# eps.net
KiCad netlist of a schematic drawn in EAGLE
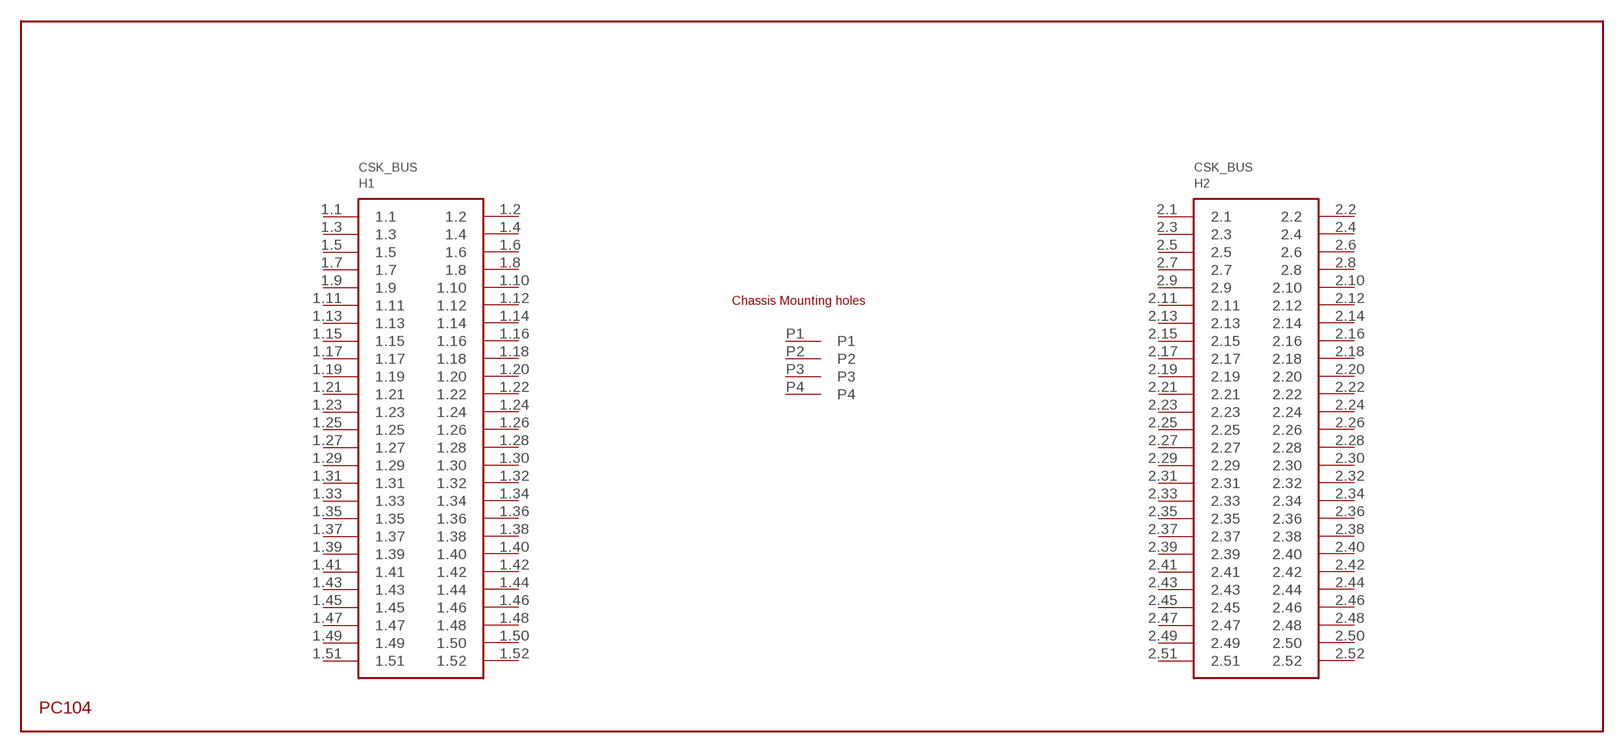
[diagram p0: schematic, sheet 1]
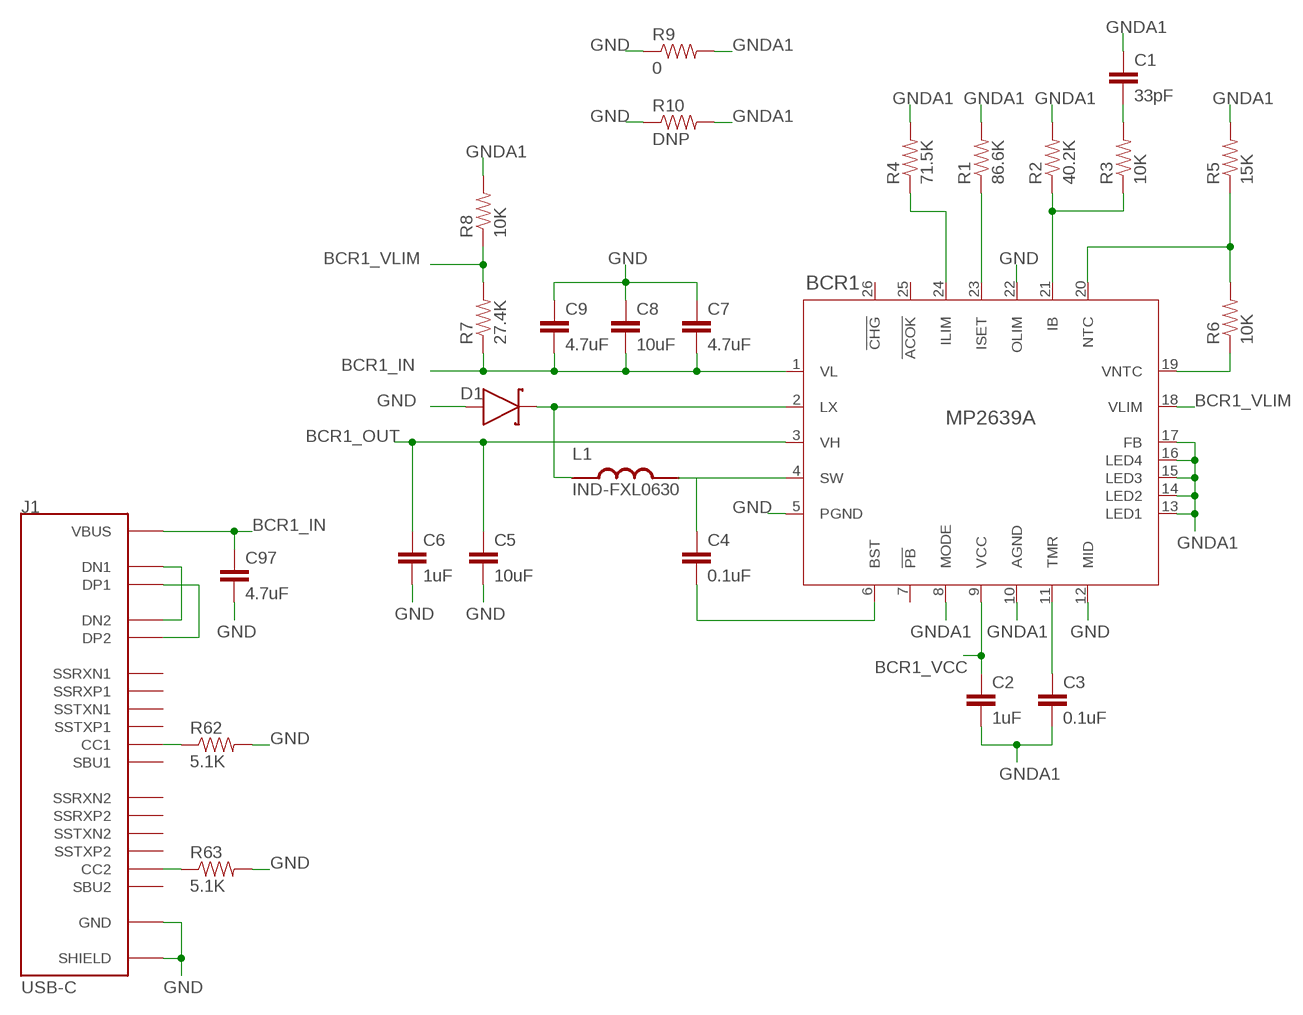
[diagram p1: schematic, sheet 2]
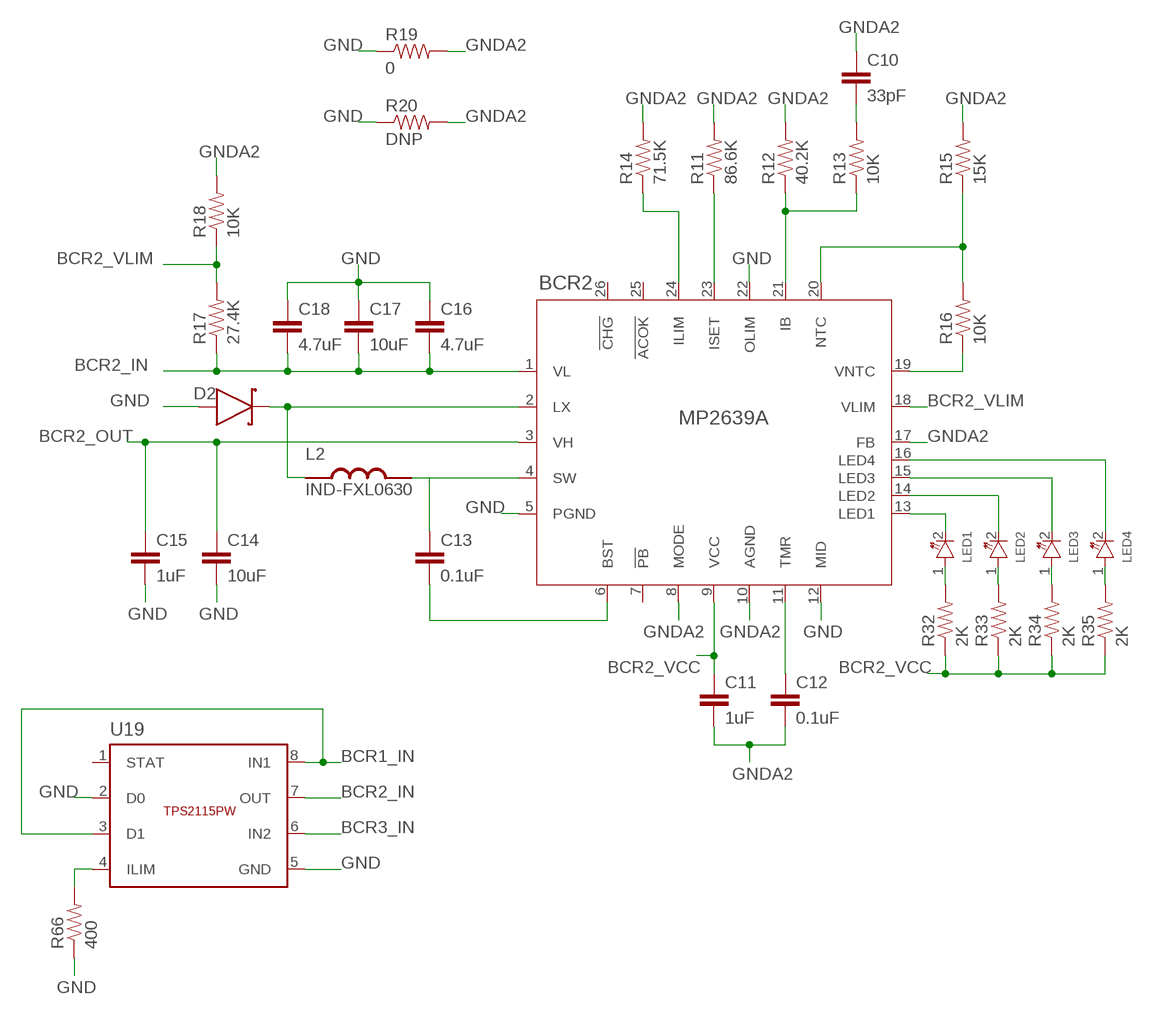
[diagram p2: schematic, sheet 3]
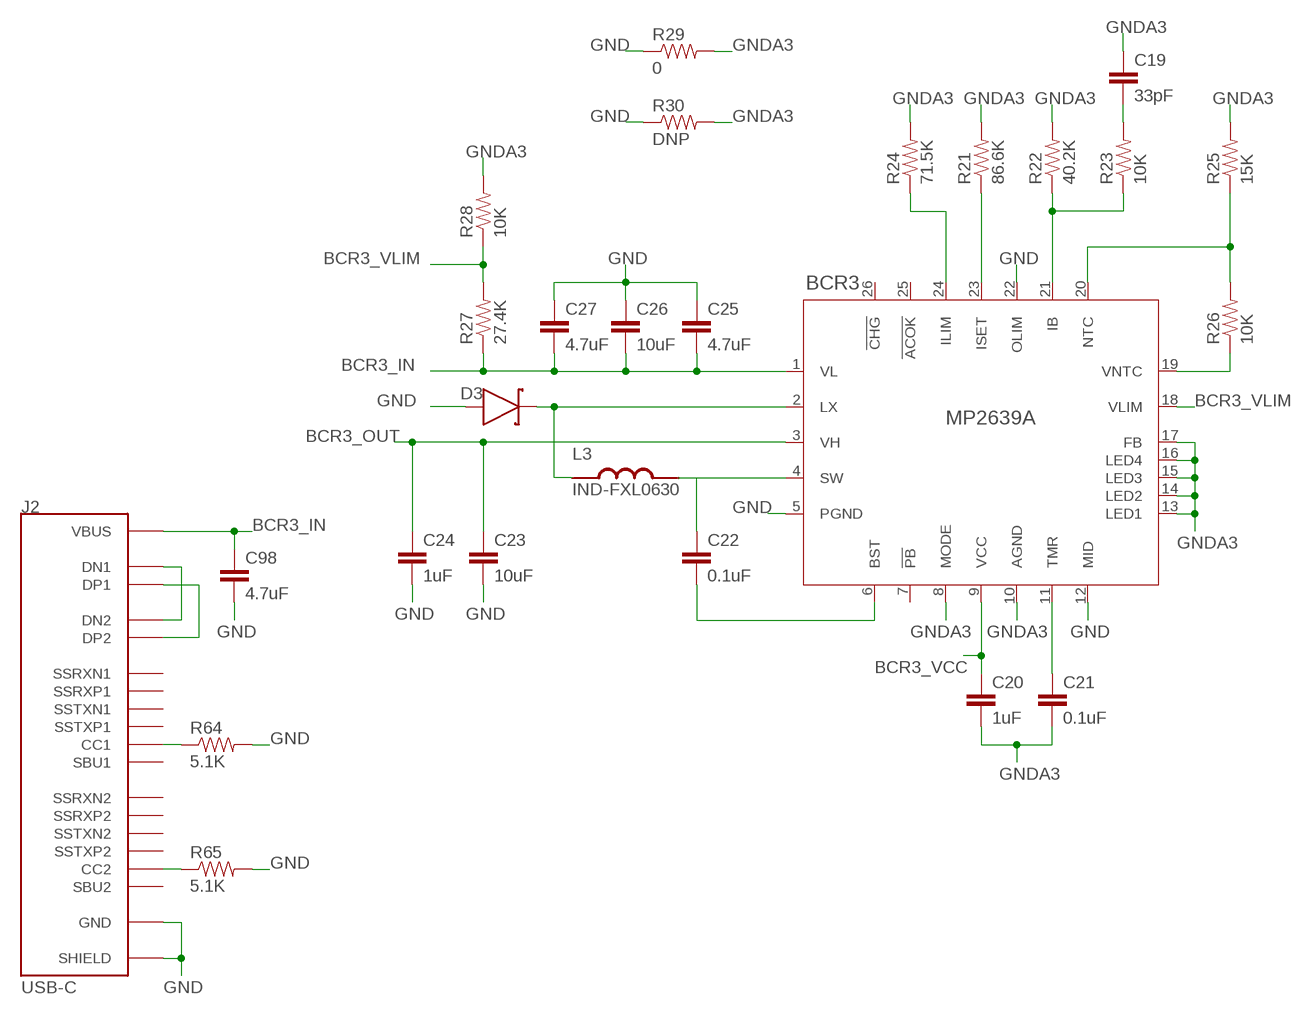
[diagram p3: schematic, sheet 4]
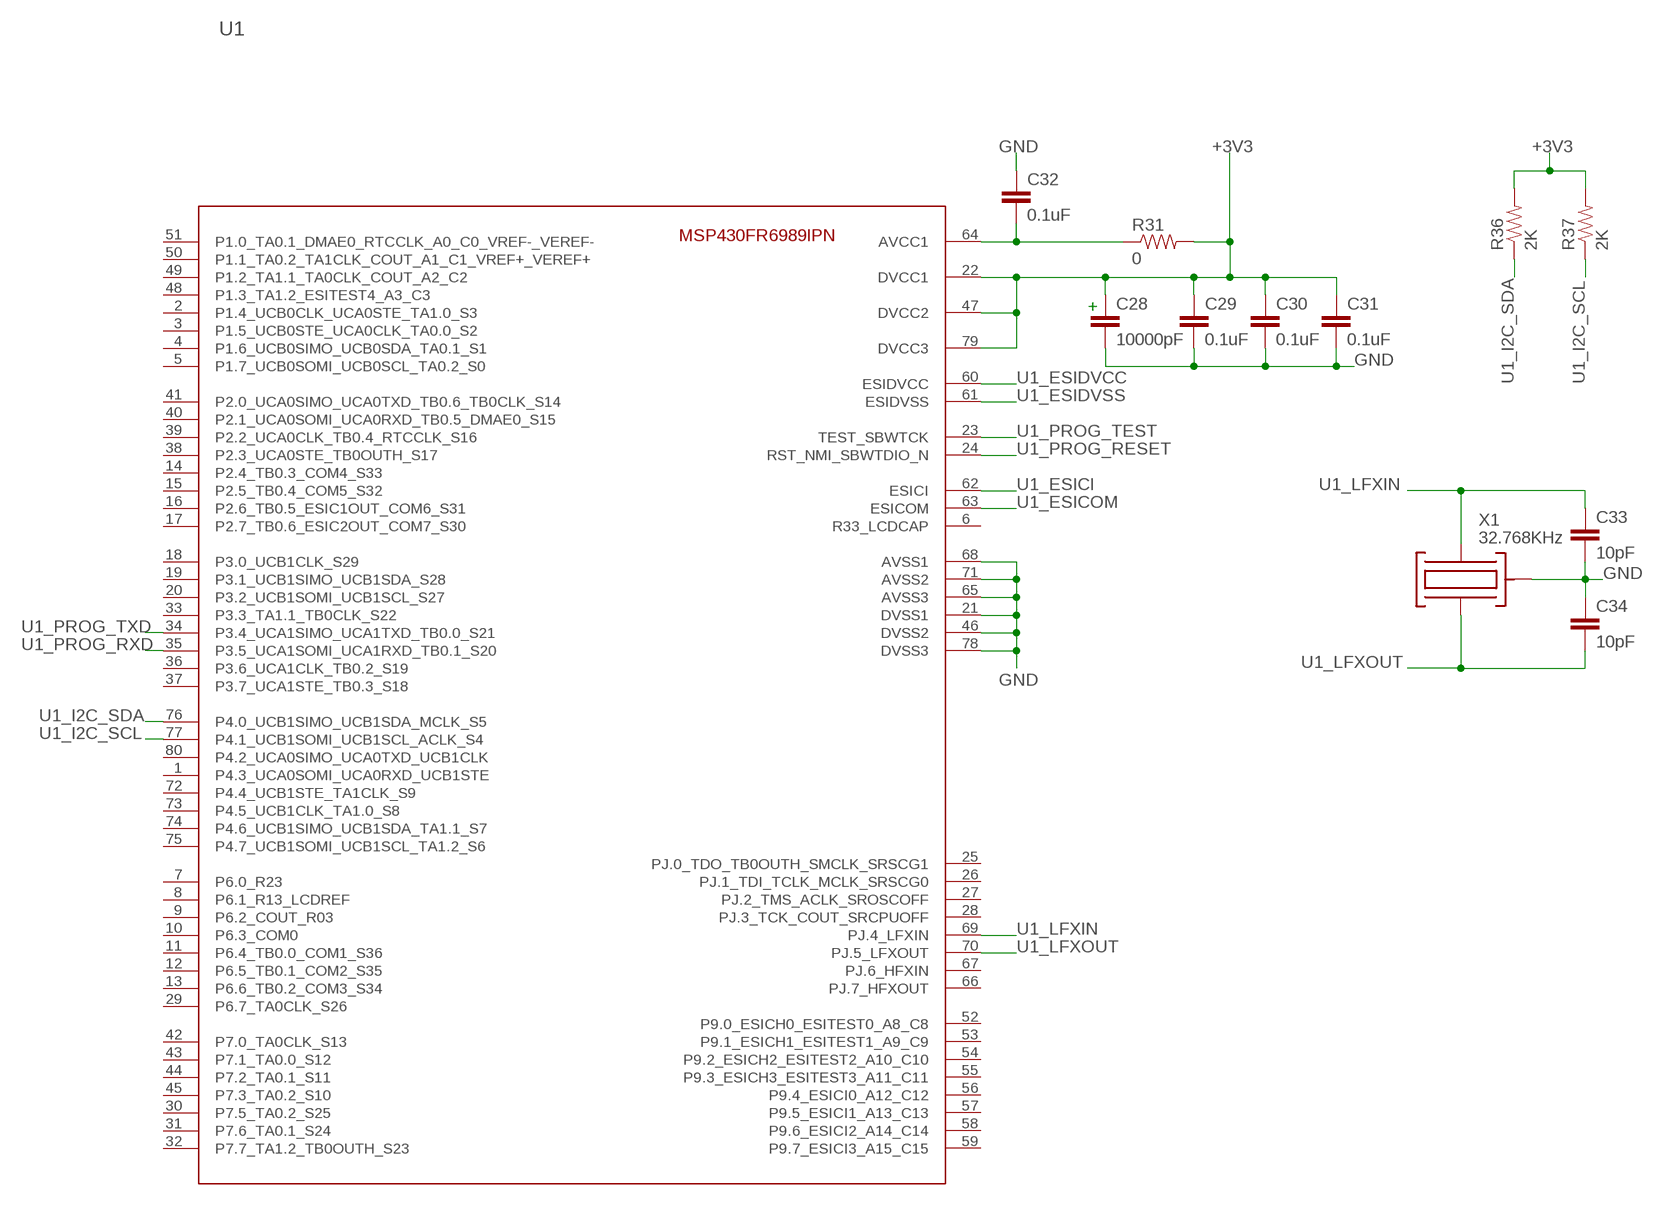
[diagram p4: schematic, sheet 5]
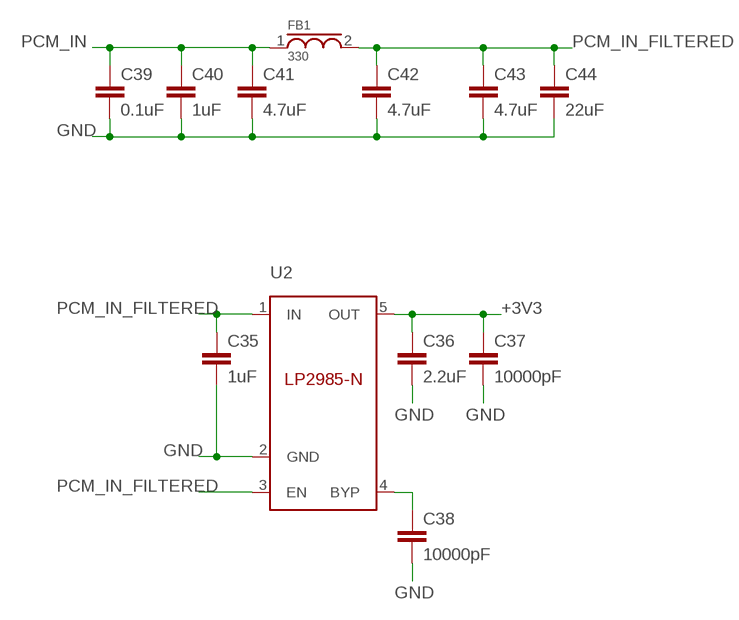
[diagram p5: schematic, sheet 6]
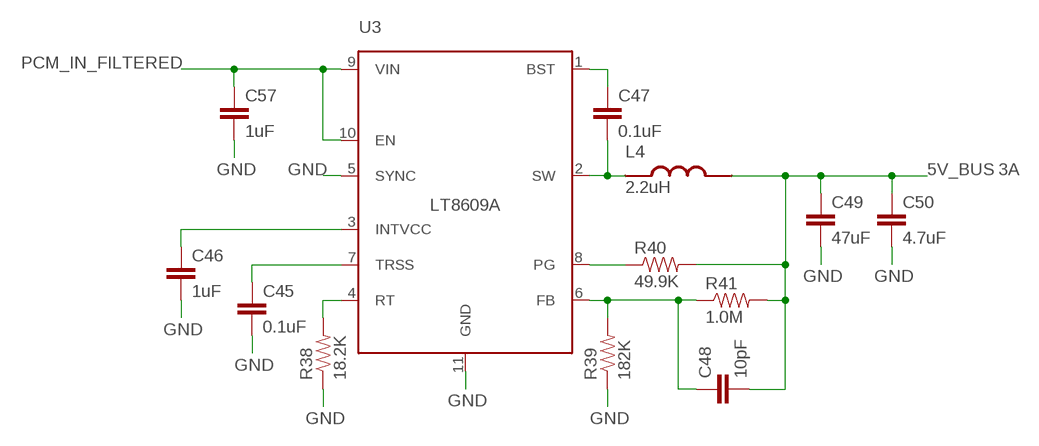
[diagram p6: schematic, sheet 7]
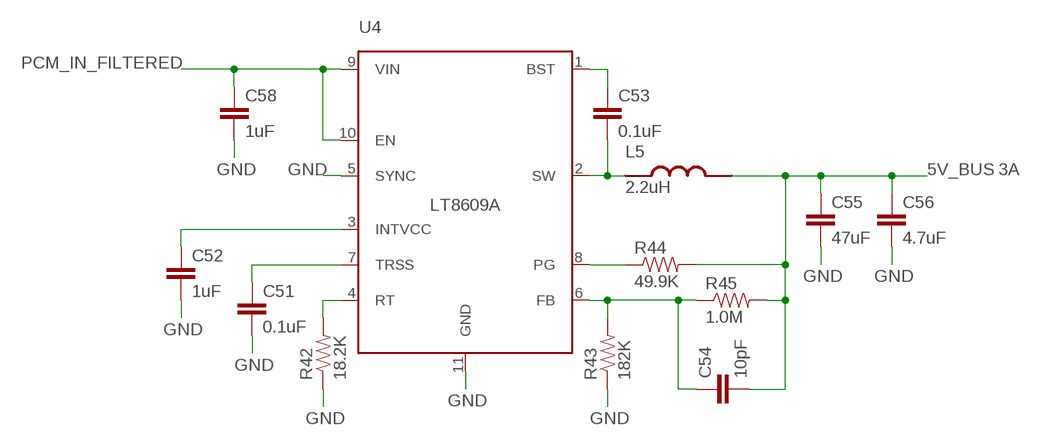
[diagram p7: schematic, sheet 8]
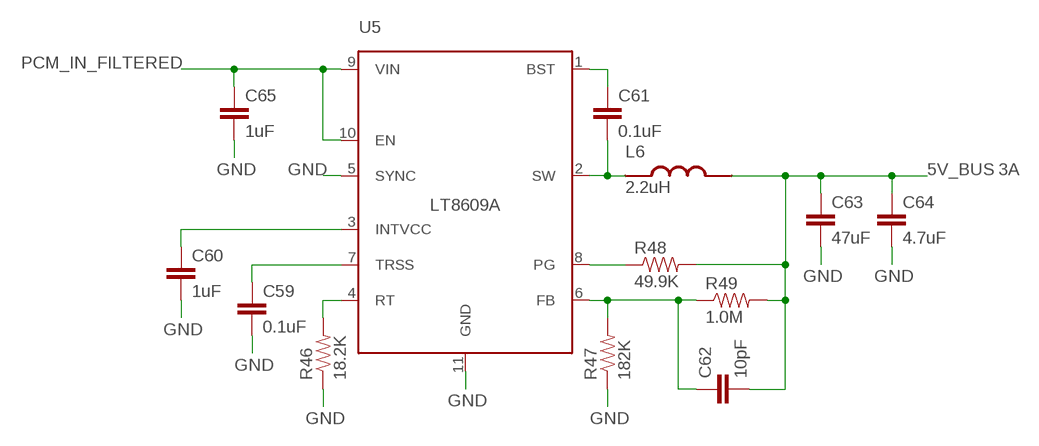
[diagram p8: schematic, sheet 9]
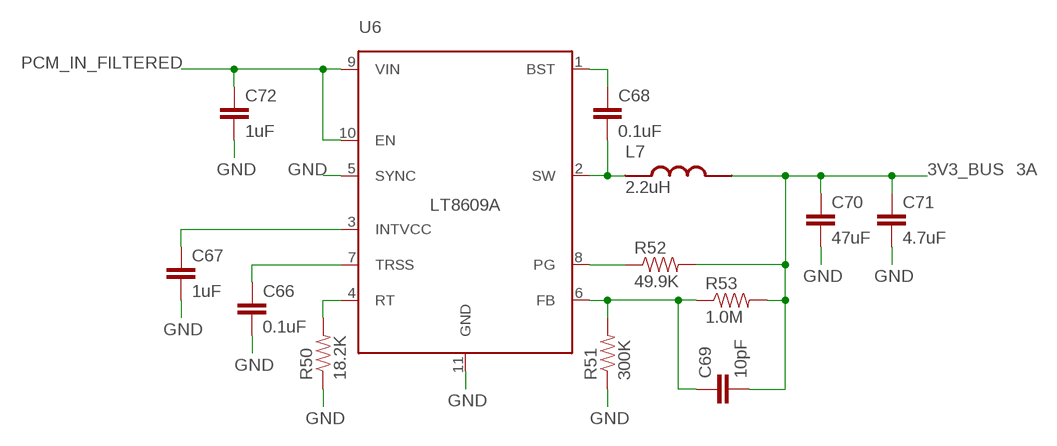
[diagram p9: schematic, sheet 10]
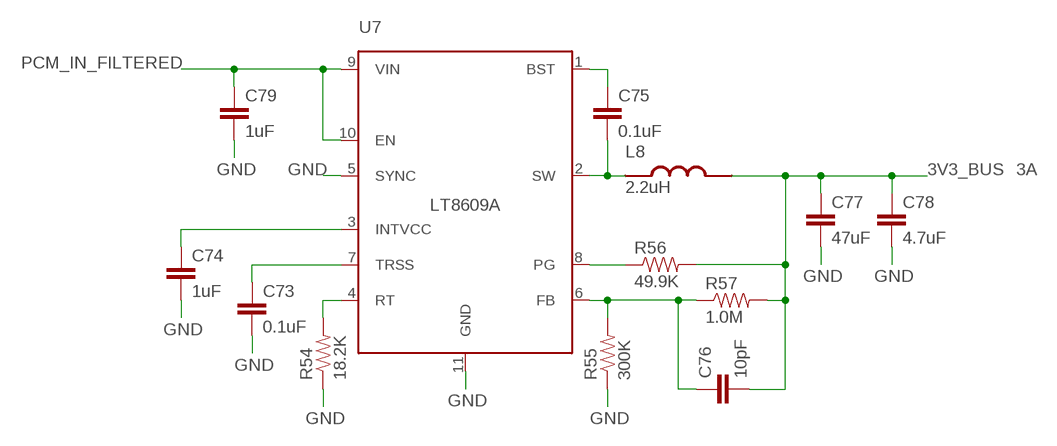
[diagram p10: schematic, sheet 11]
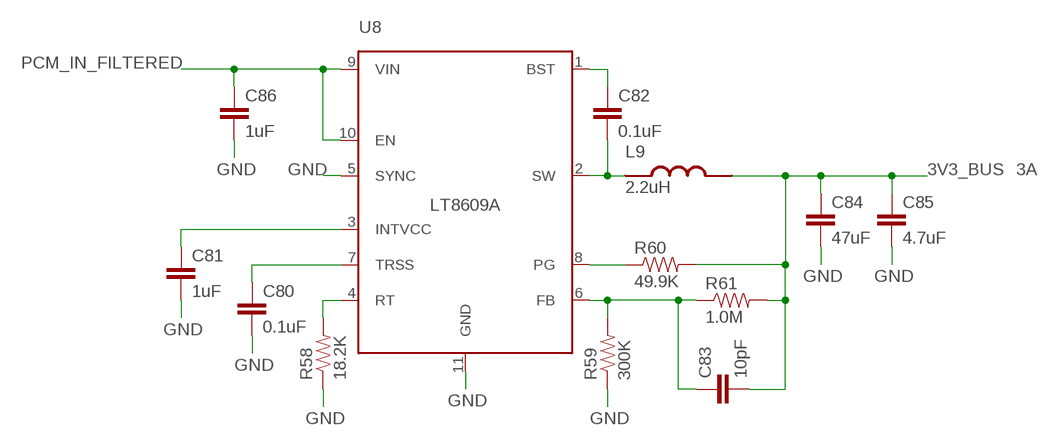
[diagram p11: schematic, sheet 12]
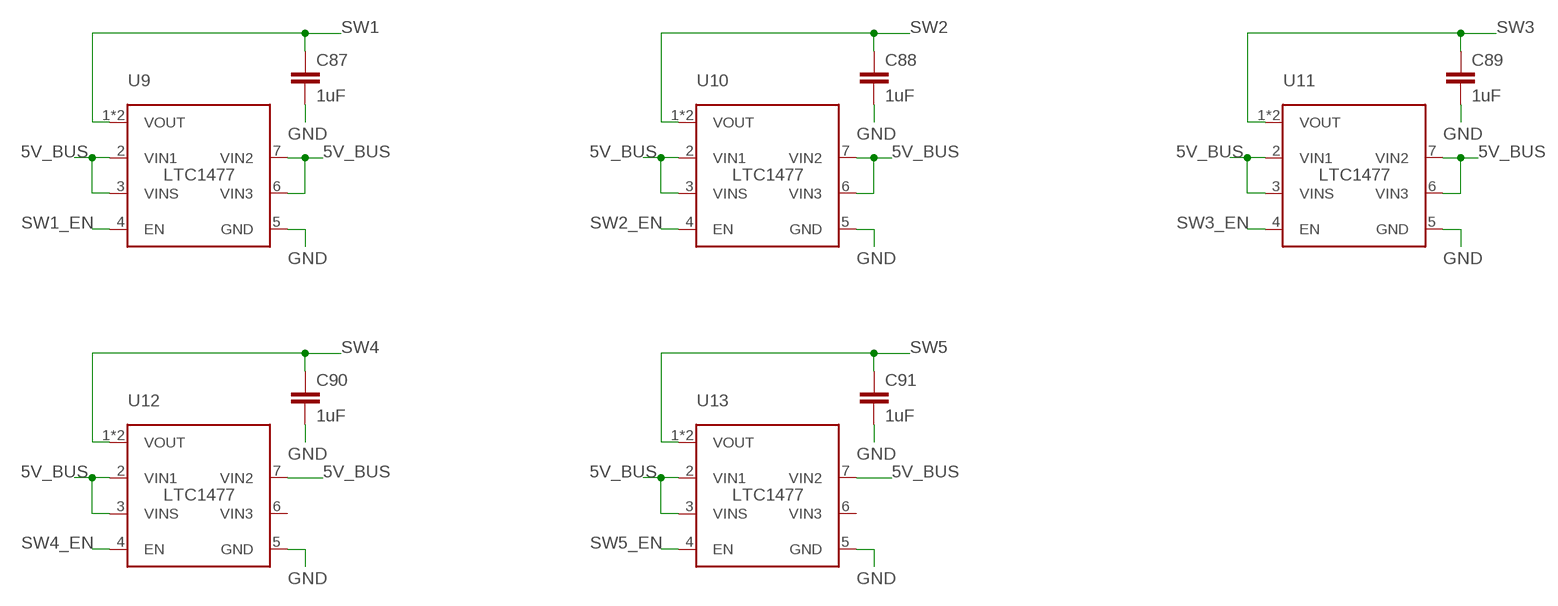
[diagram p12: schematic, sheet 13]
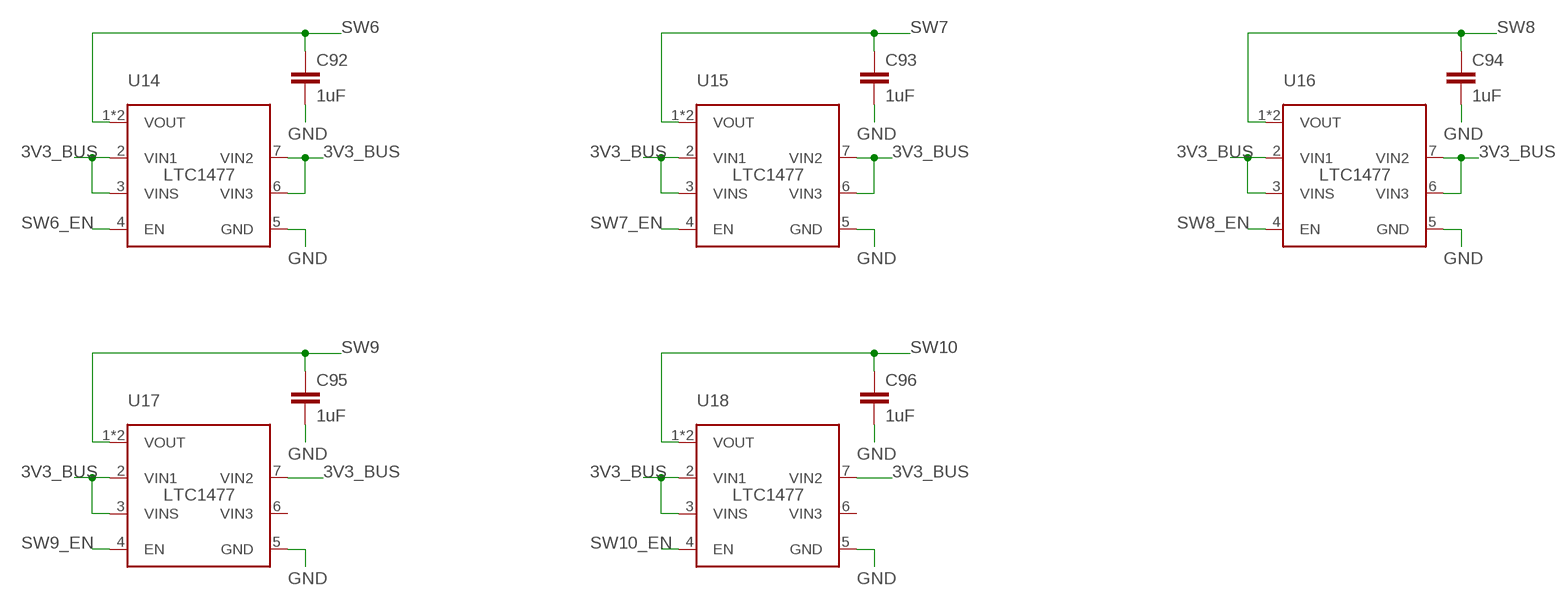
[diagram p13: schematic, sheet 14]

(export (version "E")
  (design (tool "Eeschema 10.0.6"))
  (components
    (comp (ref "H1")
      (value "PC104_WCONN")
      (footprint "eagle-import:PC104_WCONN")
      (libsource (lib "eagle-import") (part "PC104_WCONN"))
    )
    (comp (ref "C51")
      (value "0.1uF")
      (footprint "eagle-import:0603-CAP")
      (libsource (lib "eagle-import") (part "DSD_Passive_Library_CAP0603-CAP"))
    )
    (comp (ref "C52")
      (value "1uF")
      (footprint "eagle-import:0603-CAP")
      (libsource (lib "eagle-import") (part "DSD_Passive_Library_CAP0603-CAP"))
    )
    (comp (ref "C53")
      (value "0.1uF")
      (footprint "eagle-import:0603-CAP")
      (libsource (lib "eagle-import") (part "DSD_Passive_Library_CAP0603-CAP"))
    )
    (comp (ref "C54")
      (value "10pF")
      (footprint "eagle-import:0603-CAP")
      (libsource (lib "eagle-import") (part "DSD_Passive_Library_CAP0603-CAP"))
    )
    (comp (ref "C55")
      (value "47uF")
      (footprint "eagle-import:0805")
      (libsource (lib "eagle-import") (part "DSD_Passive_Library_CAP0805"))
    )
    (comp (ref "C56")
      (value "4.7uF")
      (footprint "eagle-import:0603-CAP")
      (libsource (lib "eagle-import") (part "DSD_Passive_Library_CAP0603-CAP"))
    )
    (comp (ref "C58")
      (value "1uF")
      (footprint "eagle-import:0603-CAP")
      (libsource (lib "eagle-import") (part "DSD_Passive_Library_CAP0603-CAP"))
    )
    (comp (ref "L5")
      (value "2.2uH")
      (footprint "eagle-import:XFL4020")
      (libsource (lib "eagle-import") (part "IND-XFL4020"))
    )
    (comp (ref "R42")
      (value "18.2K")
      (footprint "eagle-import:0603-RES")
      (libsource (lib "eagle-import") (part "RESISTOR0603-RES"))
    )
    (comp (ref "R43")
      (value "182K")
      (footprint "eagle-import:0603-RES")
      (libsource (lib "eagle-import") (part "RESISTOR0603-RES"))
    )
    (comp (ref "R44")
      (value "49.9K")
      (footprint "eagle-import:0603-RES")
      (libsource (lib "eagle-import") (part "RESISTOR0603-RES"))
    )
    (comp (ref "R45")
      (value "1.0M")
      (footprint "eagle-import:0603-RES")
      (libsource (lib "eagle-import") (part "RESISTOR0603-RES"))
    )
    (comp (ref "U4")
      (value "LT8609A")
      (footprint "eagle-import:MSOP-10_MSE")
      (libsource (lib "eagle-import") (part "LT8609A"))
    )
    (comp (ref "C87")
      (value "1uF")
      (footprint "eagle-import:0603-CAP")
      (libsource (lib "eagle-import") (part "DSD_Passive_Library_CAP0603-CAP"))
    )
    (comp (ref "C88")
      (value "1uF")
      (footprint "eagle-import:0603-CAP")
      (libsource (lib "eagle-import") (part "DSD_Passive_Library_CAP0603-CAP"))
    )
    (comp (ref "C89")
      (value "1uF")
      (footprint "eagle-import:0603-CAP")
      (libsource (lib "eagle-import") (part "DSD_Passive_Library_CAP0603-CAP"))
    )
    (comp (ref "C90")
      (value "1uF")
      (footprint "eagle-import:0603-CAP")
      (libsource (lib "eagle-import") (part "DSD_Passive_Library_CAP0603-CAP"))
    )
    (comp (ref "C91")
      (value "1uF")
      (footprint "eagle-import:0603-CAP")
      (libsource (lib "eagle-import") (part "DSD_Passive_Library_CAP0603-CAP"))
    )
    (comp (ref "U9")
      (value "LTC1477")
      (footprint "eagle-import:SO8")
      (libsource (lib "eagle-import") (part "LTC1477"))
    )
    (comp (ref "U10")
      (value "LTC1477")
      (footprint "eagle-import:SO8")
      (libsource (lib "eagle-import") (part "LTC1477"))
    )
    (comp (ref "U11")
      (value "LTC1477")
      (footprint "eagle-import:SO8")
      (libsource (lib "eagle-import") (part "LTC1477"))
    )
    (comp (ref "U12")
      (value "LTC1477")
      (footprint "eagle-import:SO8")
      (libsource (lib "eagle-import") (part "LTC1477"))
    )
    (comp (ref "U13")
      (value "LTC1477")
      (footprint "eagle-import:SO8")
      (libsource (lib "eagle-import") (part "LTC1477"))
    )
    (comp (ref "BCR2")
      (value "MP2639A")
      (footprint "eagle-import:IC26_MP2639A_MNP")
      (fields (field (name "COPYRIGHT") "Copyright (C) 2021 DSD. All rights reserved"))
      (libsource (lib "eagle-import") (part "MP2639A"))
    )
    (comp (ref "C10")
      (value "33pF")
      (footprint "eagle-import:0603-CAP")
      (libsource (lib "eagle-import") (part "CAP0603-CAP"))
    )
    (comp (ref "C11")
      (value "1uF")
      (footprint "eagle-import:0603-CAP")
      (libsource (lib "eagle-import") (part "CAP0603-CAP"))
    )
    (comp (ref "C12")
      (value "0.1uF")
      (footprint "eagle-import:0603-CAP")
      (libsource (lib "eagle-import") (part "CAP0603-CAP"))
    )
    (comp (ref "C13")
      (value "0.1uF")
      (footprint "eagle-import:0603-CAP")
      (libsource (lib "eagle-import") (part "CAP0603-CAP"))
    )
    (comp (ref "C14")
      (value "10uF")
      (footprint "eagle-import:0603-CAP")
      (libsource (lib "eagle-import") (part "CAP0603-CAP"))
    )
    (comp (ref "C15")
      (value "1uF")
      (footprint "eagle-import:0603-CAP")
      (libsource (lib "eagle-import") (part "CAP0603-CAP"))
    )
    (comp (ref "C16")
      (value "4.7uF")
      (footprint "eagle-import:0603-CAP")
      (libsource (lib "eagle-import") (part "CAP0603-CAP"))
    )
    (comp (ref "C17")
      (value "10uF")
      (footprint "eagle-import:0603-CAP")
      (libsource (lib "eagle-import") (part "CAP0603-CAP"))
    )
    (comp (ref "C18")
      (value "4.7uF")
      (footprint "eagle-import:0603-CAP")
      (libsource (lib "eagle-import") (part "CAP0603-CAP"))
    )
    (comp (ref "D2")
      (value "DIODE-SOD123")
      (footprint "eagle-import:SOD123")
      (libsource (lib "eagle-import") (part "DIODE-SOD123"))
    )
    (comp (ref "L2")
      (value "IND-FXL0630")
      (footprint "eagle-import:FXL0630")
      (libsource (lib "eagle-import") (part "IND-FXL0630"))
    )
    (comp (ref "LED1")
      (value "LED_0805")
      (footprint "eagle-import:LED_0805")
      (libsource (lib "eagle-import") (part "LED_0805"))
    )
    (comp (ref "LED2")
      (value "LED_0805")
      (footprint "eagle-import:LED_0805")
      (libsource (lib "eagle-import") (part "LED_0805"))
    )
    (comp (ref "LED3")
      (value "LED_0805")
      (footprint "eagle-import:LED_0805")
      (libsource (lib "eagle-import") (part "LED_0805"))
    )
    (comp (ref "LED4")
      (value "LED_0805")
      (footprint "eagle-import:LED_0805")
      (libsource (lib "eagle-import") (part "LED_0805"))
    )
    (comp (ref "R11")
      (value "86.6K")
      (footprint "eagle-import:0603-RES")
      (libsource (lib "eagle-import") (part "RESISTOR0603-RES"))
    )
    (comp (ref "R12")
      (value "40.2K")
      (footprint "eagle-import:0603-RES")
      (libsource (lib "eagle-import") (part "RESISTOR0603-RES"))
    )
    (comp (ref "R13")
      (value "10K")
      (footprint "eagle-import:0603-RES")
      (libsource (lib "eagle-import") (part "RESISTOR0603-RES"))
    )
    (comp (ref "R14")
      (value "71.5K")
      (footprint "eagle-import:0603-RES")
      (libsource (lib "eagle-import") (part "RESISTOR0603-RES"))
    )
    (comp (ref "R15")
      (value "15K")
      (footprint "eagle-import:0603-RES")
      (libsource (lib "eagle-import") (part "RESISTOR0603-RES"))
    )
    (comp (ref "R16")
      (value "10K")
      (footprint "eagle-import:0603-RES")
      (libsource (lib "eagle-import") (part "RESISTOR0603-RES"))
    )
    (comp (ref "R17")
      (value "27.4K")
      (footprint "eagle-import:0603-RES")
      (libsource (lib "eagle-import") (part "RESISTOR0603-RES"))
    )
    (comp (ref "R18")
      (value "10K")
      (footprint "eagle-import:0603-RES")
      (libsource (lib "eagle-import") (part "RESISTOR0603-RES"))
    )
    (comp (ref "R19")
      (value "0")
      (footprint "eagle-import:0603-RES")
      (libsource (lib "eagle-import") (part "RESISTOR0603-RES"))
    )
    (comp (ref "R20")
      (value "DNP")
      (footprint "eagle-import:0603-RES")
      (libsource (lib "eagle-import") (part "RESISTOR0603-RES"))
    )
    (comp (ref "R32")
      (value "2K")
      (footprint "eagle-import:0603-RES")
      (libsource (lib "eagle-import") (part "RESISTOR0603-RES"))
    )
    (comp (ref "R33")
      (value "2K")
      (footprint "eagle-import:0603-RES")
      (libsource (lib "eagle-import") (part "RESISTOR0603-RES"))
    )
    (comp (ref "R34")
      (value "2K")
      (footprint "eagle-import:0603-RES")
      (libsource (lib "eagle-import") (part "RESISTOR0603-RES"))
    )
    (comp (ref "R35")
      (value "2K")
      (footprint "eagle-import:0603-RES")
      (libsource (lib "eagle-import") (part "RESISTOR0603-RES"))
    )
    (comp (ref "R66")
      (value "400")
      (footprint "eagle-import:0603-RES")
      (libsource (lib "eagle-import") (part "RESISTOR0603-RES"))
    )
    (comp (ref "U19")
      (value "TPS2115PW")
      (footprint "eagle-import:TTSOP-8")
      (libsource (lib "eagle-import") (part "TPS2115PW"))
    )
    (comp (ref "C45")
      (value "0.1uF")
      (footprint "eagle-import:0603-CAP")
      (libsource (lib "eagle-import") (part "DSD_Passive_Library_CAP0603-CAP"))
    )
    (comp (ref "C46")
      (value "1uF")
      (footprint "eagle-import:0603-CAP")
      (libsource (lib "eagle-import") (part "DSD_Passive_Library_CAP0603-CAP"))
    )
    (comp (ref "C47")
      (value "0.1uF")
      (footprint "eagle-import:0603-CAP")
      (libsource (lib "eagle-import") (part "DSD_Passive_Library_CAP0603-CAP"))
    )
    (comp (ref "C48")
      (value "10pF")
      (footprint "eagle-import:0603-CAP")
      (libsource (lib "eagle-import") (part "DSD_Passive_Library_CAP0603-CAP"))
    )
    (comp (ref "C49")
      (value "47uF")
      (footprint "eagle-import:0805")
      (libsource (lib "eagle-import") (part "DSD_Passive_Library_CAP0805"))
    )
    (comp (ref "C50")
      (value "4.7uF")
      (footprint "eagle-import:0603-CAP")
      (libsource (lib "eagle-import") (part "DSD_Passive_Library_CAP0603-CAP"))
    )
    (comp (ref "C57")
      (value "1uF")
      (footprint "eagle-import:0603-CAP")
      (libsource (lib "eagle-import") (part "DSD_Passive_Library_CAP0603-CAP"))
    )
    (comp (ref "L4")
      (value "2.2uH")
      (footprint "eagle-import:XFL4020")
      (libsource (lib "eagle-import") (part "IND-XFL4020"))
    )
    (comp (ref "R38")
      (value "18.2K")
      (footprint "eagle-import:0603-RES")
      (libsource (lib "eagle-import") (part "RESISTOR0603-RES"))
    )
    (comp (ref "R39")
      (value "182K")
      (footprint "eagle-import:0603-RES")
      (libsource (lib "eagle-import") (part "RESISTOR0603-RES"))
    )
    (comp (ref "R40")
      (value "49.9K")
      (footprint "eagle-import:0603-RES")
      (libsource (lib "eagle-import") (part "RESISTOR0603-RES"))
    )
    (comp (ref "R41")
      (value "1.0M")
      (footprint "eagle-import:0603-RES")
      (libsource (lib "eagle-import") (part "RESISTOR0603-RES"))
    )
    (comp (ref "U3")
      (value "LT8609A")
      (footprint "eagle-import:MSOP-10_MSE")
      (libsource (lib "eagle-import") (part "LT8609A"))
    )
    (comp (ref "C35")
      (value "1uF")
      (footprint "eagle-import:0603-CAP")
      (libsource (lib "eagle-import") (part "DSD_Passive_Library_CAP0603-CAP"))
    )
    (comp (ref "C36")
      (value "2.2uF")
      (footprint "eagle-import:0603-CAP")
      (libsource (lib "eagle-import") (part "DSD_Passive_Library_CAP0603-CAP"))
    )
    (comp (ref "C37")
      (value "10000pF")
      (footprint "eagle-import:0603-CAP")
      (libsource (lib "eagle-import") (part "DSD_Passive_Library_CAP0603-CAP"))
    )
    (comp (ref "C38")
      (value "10000pF")
      (footprint "eagle-import:0603-CAP")
      (libsource (lib "eagle-import") (part "DSD_Passive_Library_CAP0603-CAP"))
    )
    (comp (ref "C39")
      (value "0.1uF")
      (footprint "eagle-import:0603-CAP")
      (libsource (lib "eagle-import") (part "DSD_Passive_Library_CAP0603-CAP"))
    )
    (comp (ref "C40")
      (value "1uF")
      (footprint "eagle-import:0603-CAP")
      (libsource (lib "eagle-import") (part "DSD_Passive_Library_CAP0603-CAP"))
    )
    (comp (ref "C41")
      (value "4.7uF")
      (footprint "eagle-import:1206")
      (libsource (lib "eagle-import") (part "DSD_Passive_Library_CAP1206"))
    )
    (comp (ref "C42")
      (value "4.7uF")
      (footprint "eagle-import:1206")
      (libsource (lib "eagle-import") (part "DSD_Passive_Library_CAP1206"))
    )
    (comp (ref "C43")
      (value "4.7uF")
      (footprint "eagle-import:1206")
      (libsource (lib "eagle-import") (part "DSD_Passive_Library_CAP1206"))
    )
    (comp (ref "C44")
      (value "22uF")
      (footprint "eagle-import:2917")
      (libsource (lib "eagle-import") (part "CAP_TANTALUM"))
    )
    (comp (ref "FB1")
      (value "330")
      (footprint "eagle-import:0805")
      (libsource (lib "eagle-import") (part "FB0805"))
    )
    (comp (ref "U2")
      (value "LP2985-N")
      (footprint "eagle-import:SOT23-5")
      (libsource (lib "eagle-import") (part "LP2985-N"))
    )
    (comp (ref "C66")
      (value "0.1uF")
      (footprint "eagle-import:0603-CAP")
      (libsource (lib "eagle-import") (part "DSD_Passive_Library_CAP0603-CAP"))
    )
    (comp (ref "C67")
      (value "1uF")
      (footprint "eagle-import:0603-CAP")
      (libsource (lib "eagle-import") (part "DSD_Passive_Library_CAP0603-CAP"))
    )
    (comp (ref "C68")
      (value "0.1uF")
      (footprint "eagle-import:0603-CAP")
      (libsource (lib "eagle-import") (part "DSD_Passive_Library_CAP0603-CAP"))
    )
    (comp (ref "C69")
      (value "10pF")
      (footprint "eagle-import:0603-CAP")
      (libsource (lib "eagle-import") (part "DSD_Passive_Library_CAP0603-CAP"))
    )
    (comp (ref "C70")
      (value "47uF")
      (footprint "eagle-import:0805")
      (libsource (lib "eagle-import") (part "DSD_Passive_Library_CAP0805"))
    )
    (comp (ref "C71")
      (value "4.7uF")
      (footprint "eagle-import:0603-CAP")
      (libsource (lib "eagle-import") (part "DSD_Passive_Library_CAP0603-CAP"))
    )
    (comp (ref "C72")
      (value "1uF")
      (footprint "eagle-import:0603-CAP")
      (libsource (lib "eagle-import") (part "DSD_Passive_Library_CAP0603-CAP"))
    )
    (comp (ref "L7")
      (value "2.2uH")
      (footprint "eagle-import:XFL4020")
      (libsource (lib "eagle-import") (part "IND-XFL4020"))
    )
    (comp (ref "R50")
      (value "18.2K")
      (footprint "eagle-import:0603-RES")
      (libsource (lib "eagle-import") (part "RESISTOR0603-RES"))
    )
    (comp (ref "R51")
      (value "300K")
      (footprint "eagle-import:0603-RES")
      (libsource (lib "eagle-import") (part "RESISTOR0603-RES"))
    )
    (comp (ref "R52")
      (value "49.9K")
      (footprint "eagle-import:0603-RES")
      (libsource (lib "eagle-import") (part "RESISTOR0603-RES"))
    )
    (comp (ref "R53")
      (value "1.0M")
      (footprint "eagle-import:0603-RES")
      (libsource (lib "eagle-import") (part "RESISTOR0603-RES"))
    )
    (comp (ref "U6")
      (value "LT8609A")
      (footprint "eagle-import:MSOP-10_MSE")
      (libsource (lib "eagle-import") (part "LT8609A"))
    )
    (comp (ref "BCR1")
      (value "MP2639A")
      (footprint "eagle-import:IC26_MP2639A_MNP")
      (fields (field (name "COPYRIGHT") "Copyright (C) 2021 DSD. All rights reserved"))
      (libsource (lib "eagle-import") (part "MP2639A"))
    )
    (comp (ref "C1")
      (value "33pF")
      (footprint "eagle-import:0603-CAP")
      (libsource (lib "eagle-import") (part "CAP0603-CAP"))
    )
    (comp (ref "C2")
      (value "1uF")
      (footprint "eagle-import:0603-CAP")
      (libsource (lib "eagle-import") (part "CAP0603-CAP"))
    )
    (comp (ref "C3")
      (value "0.1uF")
      (footprint "eagle-import:0603-CAP")
      (libsource (lib "eagle-import") (part "CAP0603-CAP"))
    )
    (comp (ref "C4")
      (value "0.1uF")
      (footprint "eagle-import:0603-CAP")
      (libsource (lib "eagle-import") (part "CAP0603-CAP"))
    )
    (comp (ref "C5")
      (value "10uF")
      (footprint "eagle-import:0603-CAP")
      (libsource (lib "eagle-import") (part "CAP0603-CAP"))
    )
    (comp (ref "C6")
      (value "1uF")
      (footprint "eagle-import:0603-CAP")
      (libsource (lib "eagle-import") (part "CAP0603-CAP"))
    )
    (comp (ref "C7")
      (value "4.7uF")
      (footprint "eagle-import:0603-CAP")
      (libsource (lib "eagle-import") (part "CAP0603-CAP"))
    )
    (comp (ref "C8")
      (value "10uF")
      (footprint "eagle-import:0603-CAP")
      (libsource (lib "eagle-import") (part "CAP0603-CAP"))
    )
    (comp (ref "C9")
      (value "4.7uF")
      (footprint "eagle-import:0603-CAP")
      (libsource (lib "eagle-import") (part "CAP0603-CAP"))
    )
    (comp (ref "C97")
      (value "4.7uF")
      (footprint "eagle-import:0603-CAP")
      (libsource (lib "eagle-import") (part "DSD_Passive_Library_CAP0603-CAP"))
    )
    (comp (ref "D1")
      (value "DIODE-SOD123")
      (footprint "eagle-import:SOD123")
      (libsource (lib "eagle-import") (part "DIODE-SOD123"))
    )
    (comp (ref "J1")
      (value "USB-C")
      (footprint "eagle-import:CUI_UJ31-CH-G1-SMT-TR")
      (fields (field (name "MF") "CUI Devices") (field (name "MP") "UJ31-CH-G1-SMT-TR"))
      (libsource (lib "eagle-import") (part "USB-C"))
    )
    (comp (ref "L1")
      (value "IND-FXL0630")
      (footprint "eagle-import:FXL0630")
      (libsource (lib "eagle-import") (part "IND-FXL0630"))
    )
    (comp (ref "R1")
      (value "86.6K")
      (footprint "eagle-import:0603-RES")
      (libsource (lib "eagle-import") (part "RESISTOR0603-RES"))
    )
    (comp (ref "R2")
      (value "40.2K")
      (footprint "eagle-import:0603-RES")
      (libsource (lib "eagle-import") (part "RESISTOR0603-RES"))
    )
    (comp (ref "R3")
      (value "10K")
      (footprint "eagle-import:0603-RES")
      (libsource (lib "eagle-import") (part "RESISTOR0603-RES"))
    )
    (comp (ref "R4")
      (value "71.5K")
      (footprint "eagle-import:0603-RES")
      (libsource (lib "eagle-import") (part "RESISTOR0603-RES"))
    )
    (comp (ref "R5")
      (value "15K")
      (footprint "eagle-import:0603-RES")
      (libsource (lib "eagle-import") (part "RESISTOR0603-RES"))
    )
    (comp (ref "R6")
      (value "10K")
      (footprint "eagle-import:0603-RES")
      (libsource (lib "eagle-import") (part "RESISTOR0603-RES"))
    )
    (comp (ref "R7")
      (value "27.4K")
      (footprint "eagle-import:0603-RES")
      (libsource (lib "eagle-import") (part "RESISTOR0603-RES"))
    )
    (comp (ref "R8")
      (value "10K")
      (footprint "eagle-import:0603-RES")
      (libsource (lib "eagle-import") (part "RESISTOR0603-RES"))
    )
    (comp (ref "R9")
      (value "0")
      (footprint "eagle-import:0603-RES")
      (libsource (lib "eagle-import") (part "RESISTOR0603-RES"))
    )
    (comp (ref "R10")
      (value "DNP")
      (footprint "eagle-import:0603-RES")
      (libsource (lib "eagle-import") (part "RESISTOR0603-RES"))
    )
    (comp (ref "R62")
      (value "5.1K")
      (footprint "eagle-import:0603-RES")
      (libsource (lib "eagle-import") (part "RESISTOR0603-RES"))
    )
    (comp (ref "R63")
      (value "5.1K")
      (footprint "eagle-import:0603-RES")
      (libsource (lib "eagle-import") (part "RESISTOR0603-RES"))
    )
    (comp (ref "C59")
      (value "0.1uF")
      (footprint "eagle-import:0603-CAP")
      (libsource (lib "eagle-import") (part "DSD_Passive_Library_CAP0603-CAP"))
    )
    (comp (ref "C60")
      (value "1uF")
      (footprint "eagle-import:0603-CAP")
      (libsource (lib "eagle-import") (part "DSD_Passive_Library_CAP0603-CAP"))
    )
    (comp (ref "C61")
      (value "0.1uF")
      (footprint "eagle-import:0603-CAP")
      (libsource (lib "eagle-import") (part "DSD_Passive_Library_CAP0603-CAP"))
    )
    (comp (ref "C62")
      (value "10pF")
      (footprint "eagle-import:0603-CAP")
      (libsource (lib "eagle-import") (part "DSD_Passive_Library_CAP0603-CAP"))
    )
    (comp (ref "C63")
      (value "47uF")
      (footprint "eagle-import:0805")
      (libsource (lib "eagle-import") (part "DSD_Passive_Library_CAP0805"))
    )
    (comp (ref "C64")
      (value "4.7uF")
      (footprint "eagle-import:0603-CAP")
      (libsource (lib "eagle-import") (part "DSD_Passive_Library_CAP0603-CAP"))
    )
    (comp (ref "C65")
      (value "1uF")
      (footprint "eagle-import:0603-CAP")
      (libsource (lib "eagle-import") (part "DSD_Passive_Library_CAP0603-CAP"))
    )
    (comp (ref "L6")
      (value "2.2uH")
      (footprint "eagle-import:XFL4020")
      (libsource (lib "eagle-import") (part "IND-XFL4020"))
    )
    (comp (ref "R46")
      (value "18.2K")
      (footprint "eagle-import:0603-RES")
      (libsource (lib "eagle-import") (part "RESISTOR0603-RES"))
    )
    (comp (ref "R47")
      (value "182K")
      (footprint "eagle-import:0603-RES")
      (libsource (lib "eagle-import") (part "RESISTOR0603-RES"))
    )
    (comp (ref "R48")
      (value "49.9K")
      (footprint "eagle-import:0603-RES")
      (libsource (lib "eagle-import") (part "RESISTOR0603-RES"))
    )
    (comp (ref "R49")
      (value "1.0M")
      (footprint "eagle-import:0603-RES")
      (libsource (lib "eagle-import") (part "RESISTOR0603-RES"))
    )
    (comp (ref "U5")
      (value "LT8609A")
      (footprint "eagle-import:MSOP-10_MSE")
      (libsource (lib "eagle-import") (part "LT8609A"))
    )
    (comp (ref "C28")
      (value "10000pF")
      (footprint "eagle-import:0805")
      (libsource (lib "eagle-import") (part "DSD_Passive_Library_CAP0805"))
    )
    (comp (ref "C29")
      (value "0.1uF")
      (footprint "eagle-import:0603-CAP")
      (libsource (lib "eagle-import") (part "DSD_Passive_Library_CAP0603-CAP"))
    )
    (comp (ref "C30")
      (value "0.1uF")
      (footprint "eagle-import:0603-CAP")
      (libsource (lib "eagle-import") (part "DSD_Passive_Library_CAP0603-CAP"))
    )
    (comp (ref "C31")
      (value "0.1uF")
      (footprint "eagle-import:0603-CAP")
      (libsource (lib "eagle-import") (part "DSD_Passive_Library_CAP0603-CAP"))
    )
    (comp (ref "C32")
      (value "0.1uF")
      (footprint "eagle-import:0603-CAP")
      (libsource (lib "eagle-import") (part "DSD_Passive_Library_CAP0603-CAP"))
    )
    (comp (ref "C33")
      (value "10pF")
      (footprint "eagle-import:0603-CAP")
      (libsource (lib "eagle-import") (part "DSD_Passive_Library_CAP0603-CAP"))
    )
    (comp (ref "C34")
      (value "10pF")
      (footprint "eagle-import:0603-CAP")
      (libsource (lib "eagle-import") (part "DSD_Passive_Library_CAP0603-CAP"))
    )
    (comp (ref "R31")
      (value "0")
      (footprint "eagle-import:0603-RES")
      (libsource (lib "eagle-import") (part "RESISTOR0603-RES"))
    )
    (comp (ref "R36")
      (value "2K")
      (footprint "eagle-import:0603-RES")
      (libsource (lib "eagle-import") (part "RESISTOR0603-RES"))
    )
    (comp (ref "R37")
      (value "2K")
      (footprint "eagle-import:0603-RES")
      (libsource (lib "eagle-import") (part "RESISTOR0603-RES"))
    )
    (comp (ref "U1")
      (value "MSP430FR6989IPN")
      (footprint "eagle-import:PN0080A_N")
      (fields
        (field (name "AUTHOR") "Craig Opie")
        (field (name "COPYRIGHT") "Copyright (C) 2021 DSD. All rights reserved.")
      )
      (libsource (lib "eagle-import") (part "MSP430FR6989IPN"))
    )
    (comp (ref "X1")
      (value "32.768KHz")
      (footprint "eagle-import:MS3V-T1R")
      (fields (field (name "AUTHOR") "Craig Opie"))
      (libsource (lib "eagle-import") (part "MS3V-T1R"))
    )
    (comp (ref "C80")
      (value "0.1uF")
      (footprint "eagle-import:0603-CAP")
      (libsource (lib "eagle-import") (part "DSD_Passive_Library_CAP0603-CAP"))
    )
    (comp (ref "C81")
      (value "1uF")
      (footprint "eagle-import:0603-CAP")
      (libsource (lib "eagle-import") (part "DSD_Passive_Library_CAP0603-CAP"))
    )
    (comp (ref "C82")
      (value "0.1uF")
      (footprint "eagle-import:0603-CAP")
      (libsource (lib "eagle-import") (part "DSD_Passive_Library_CAP0603-CAP"))
    )
    (comp (ref "C83")
      (value "10pF")
      (footprint "eagle-import:0603-CAP")
      (libsource (lib "eagle-import") (part "DSD_Passive_Library_CAP0603-CAP"))
    )
    (comp (ref "C84")
      (value "47uF")
      (footprint "eagle-import:0805")
      (libsource (lib "eagle-import") (part "DSD_Passive_Library_CAP0805"))
    )
    (comp (ref "C85")
      (value "4.7uF")
      (footprint "eagle-import:0603-CAP")
      (libsource (lib "eagle-import") (part "DSD_Passive_Library_CAP0603-CAP"))
    )
    (comp (ref "C86")
      (value "1uF")
      (footprint "eagle-import:0603-CAP")
      (libsource (lib "eagle-import") (part "DSD_Passive_Library_CAP0603-CAP"))
    )
    (comp (ref "L9")
      (value "2.2uH")
      (footprint "eagle-import:XFL4020")
      (libsource (lib "eagle-import") (part "IND-XFL4020"))
    )
    (comp (ref "R58")
      (value "18.2K")
      (footprint "eagle-import:0603-RES")
      (libsource (lib "eagle-import") (part "RESISTOR0603-RES"))
    )
    (comp (ref "R59")
      (value "300K")
      (footprint "eagle-import:0603-RES")
      (libsource (lib "eagle-import") (part "RESISTOR0603-RES"))
    )
    (comp (ref "R60")
      (value "49.9K")
      (footprint "eagle-import:0603-RES")
      (libsource (lib "eagle-import") (part "RESISTOR0603-RES"))
    )
    (comp (ref "R61")
      (value "1.0M")
      (footprint "eagle-import:0603-RES")
      (libsource (lib "eagle-import") (part "RESISTOR0603-RES"))
    )
    (comp (ref "U8")
      (value "LT8609A")
      (footprint "eagle-import:MSOP-10_MSE")
      (libsource (lib "eagle-import") (part "LT8609A"))
    )
    (comp (ref "C92")
      (value "1uF")
      (footprint "eagle-import:0603-CAP")
      (libsource (lib "eagle-import") (part "DSD_Passive_Library_CAP0603-CAP"))
    )
    (comp (ref "C93")
      (value "1uF")
      (footprint "eagle-import:0603-CAP")
      (libsource (lib "eagle-import") (part "DSD_Passive_Library_CAP0603-CAP"))
    )
    (comp (ref "C94")
      (value "1uF")
      (footprint "eagle-import:0603-CAP")
      (libsource (lib "eagle-import") (part "DSD_Passive_Library_CAP0603-CAP"))
    )
    (comp (ref "C95")
      (value "1uF")
      (footprint "eagle-import:0603-CAP")
      (libsource (lib "eagle-import") (part "DSD_Passive_Library_CAP0603-CAP"))
    )
    (comp (ref "C96")
      (value "1uF")
      (footprint "eagle-import:0603-CAP")
      (libsource (lib "eagle-import") (part "DSD_Passive_Library_CAP0603-CAP"))
    )
    (comp (ref "U14")
      (value "LTC1477")
      (footprint "eagle-import:SO8")
      (libsource (lib "eagle-import") (part "LTC1477"))
    )
    (comp (ref "U15")
      (value "LTC1477")
      (footprint "eagle-import:SO8")
      (libsource (lib "eagle-import") (part "LTC1477"))
    )
    (comp (ref "U16")
      (value "LTC1477")
      (footprint "eagle-import:SO8")
      (libsource (lib "eagle-import") (part "LTC1477"))
    )
    (comp (ref "U17")
      (value "LTC1477")
      (footprint "eagle-import:SO8")
      (libsource (lib "eagle-import") (part "LTC1477"))
    )
    (comp (ref "U18")
      (value "LTC1477")
      (footprint "eagle-import:SO8")
      (libsource (lib "eagle-import") (part "LTC1477"))
    )
    (comp (ref "BCR3")
      (value "MP2639A")
      (footprint "eagle-import:IC26_MP2639A_MNP")
      (fields (field (name "COPYRIGHT") "Copyright (C) 2021 DSD. All rights reserved"))
      (libsource (lib "eagle-import") (part "MP2639A"))
    )
    (comp (ref "C19")
      (value "33pF")
      (footprint "eagle-import:0603-CAP")
      (libsource (lib "eagle-import") (part "CAP0603-CAP"))
    )
    (comp (ref "C20")
      (value "1uF")
      (footprint "eagle-import:0603-CAP")
      (libsource (lib "eagle-import") (part "CAP0603-CAP"))
    )
    (comp (ref "C21")
      (value "0.1uF")
      (footprint "eagle-import:0603-CAP")
      (libsource (lib "eagle-import") (part "CAP0603-CAP"))
    )
    (comp (ref "C22")
      (value "0.1uF")
      (footprint "eagle-import:0603-CAP")
      (libsource (lib "eagle-import") (part "CAP0603-CAP"))
    )
    (comp (ref "C23")
      (value "10uF")
      (footprint "eagle-import:0603-CAP")
      (libsource (lib "eagle-import") (part "CAP0603-CAP"))
    )
    (comp (ref "C24")
      (value "1uF")
      (footprint "eagle-import:0603-CAP")
      (libsource (lib "eagle-import") (part "CAP0603-CAP"))
    )
    (comp (ref "C25")
      (value "4.7uF")
      (footprint "eagle-import:0603-CAP")
      (libsource (lib "eagle-import") (part "CAP0603-CAP"))
    )
    (comp (ref "C26")
      (value "10uF")
      (footprint "eagle-import:0603-CAP")
      (libsource (lib "eagle-import") (part "CAP0603-CAP"))
    )
    (comp (ref "C27")
      (value "4.7uF")
      (footprint "eagle-import:0603-CAP")
      (libsource (lib "eagle-import") (part "CAP0603-CAP"))
    )
    (comp (ref "C98")
      (value "4.7uF")
      (footprint "eagle-import:0603-CAP")
      (libsource (lib "eagle-import") (part "DSD_Passive_Library_CAP0603-CAP"))
    )
    (comp (ref "D3")
      (value "DIODE-SOD123")
      (footprint "eagle-import:SOD123")
      (libsource (lib "eagle-import") (part "DIODE-SOD123"))
    )
    (comp (ref "J2")
      (value "USB-C")
      (footprint "eagle-import:CUI_UJ31-CH-G1-SMT-TR")
      (fields (field (name "MF") "CUI Devices") (field (name "MP") "UJ31-CH-G1-SMT-TR"))
      (libsource (lib "eagle-import") (part "USB-C"))
    )
    (comp (ref "L3")
      (value "IND-FXL0630")
      (footprint "eagle-import:FXL0630")
      (libsource (lib "eagle-import") (part "IND-FXL0630"))
    )
    (comp (ref "R21")
      (value "86.6K")
      (footprint "eagle-import:0603-RES")
      (libsource (lib "eagle-import") (part "RESISTOR0603-RES"))
    )
    (comp (ref "R22")
      (value "40.2K")
      (footprint "eagle-import:0603-RES")
      (libsource (lib "eagle-import") (part "RESISTOR0603-RES"))
    )
    (comp (ref "R23")
      (value "10K")
      (footprint "eagle-import:0603-RES")
      (libsource (lib "eagle-import") (part "RESISTOR0603-RES"))
    )
    (comp (ref "R24")
      (value "71.5K")
      (footprint "eagle-import:0603-RES")
      (libsource (lib "eagle-import") (part "RESISTOR0603-RES"))
    )
    (comp (ref "R25")
      (value "15K")
      (footprint "eagle-import:0603-RES")
      (libsource (lib "eagle-import") (part "RESISTOR0603-RES"))
    )
    (comp (ref "R26")
      (value "10K")
      (footprint "eagle-import:0603-RES")
      (libsource (lib "eagle-import") (part "RESISTOR0603-RES"))
    )
    (comp (ref "R27")
      (value "27.4K")
      (footprint "eagle-import:0603-RES")
      (libsource (lib "eagle-import") (part "RESISTOR0603-RES"))
    )
    (comp (ref "R28")
      (value "10K")
      (footprint "eagle-import:0603-RES")
      (libsource (lib "eagle-import") (part "RESISTOR0603-RES"))
    )
    (comp (ref "R29")
      (value "0")
      (footprint "eagle-import:0603-RES")
      (libsource (lib "eagle-import") (part "RESISTOR0603-RES"))
    )
    (comp (ref "R30")
      (value "DNP")
      (footprint "eagle-import:0603-RES")
      (libsource (lib "eagle-import") (part "RESISTOR0603-RES"))
    )
    (comp (ref "R64")
      (value "5.1K")
      (footprint "eagle-import:0603-RES")
      (libsource (lib "eagle-import") (part "RESISTOR0603-RES"))
    )
    (comp (ref "R65")
      (value "5.1K")
      (footprint "eagle-import:0603-RES")
      (libsource (lib "eagle-import") (part "RESISTOR0603-RES"))
    )
    (comp (ref "C73")
      (value "0.1uF")
      (footprint "eagle-import:0603-CAP")
      (libsource (lib "eagle-import") (part "DSD_Passive_Library_CAP0603-CAP"))
    )
    (comp (ref "C74")
      (value "1uF")
      (footprint "eagle-import:0603-CAP")
      (libsource (lib "eagle-import") (part "DSD_Passive_Library_CAP0603-CAP"))
    )
    (comp (ref "C75")
      (value "0.1uF")
      (footprint "eagle-import:0603-CAP")
      (libsource (lib "eagle-import") (part "DSD_Passive_Library_CAP0603-CAP"))
    )
    (comp (ref "C76")
      (value "10pF")
      (footprint "eagle-import:0603-CAP")
      (libsource (lib "eagle-import") (part "DSD_Passive_Library_CAP0603-CAP"))
    )
    (comp (ref "C77")
      (value "47uF")
      (footprint "eagle-import:0805")
      (libsource (lib "eagle-import") (part "DSD_Passive_Library_CAP0805"))
    )
    (comp (ref "C78")
      (value "4.7uF")
      (footprint "eagle-import:0603-CAP")
      (libsource (lib "eagle-import") (part "DSD_Passive_Library_CAP0603-CAP"))
    )
    (comp (ref "C79")
      (value "1uF")
      (footprint "eagle-import:0603-CAP")
      (libsource (lib "eagle-import") (part "DSD_Passive_Library_CAP0603-CAP"))
    )
    (comp (ref "L8")
      (value "2.2uH")
      (footprint "eagle-import:XFL4020")
      (libsource (lib "eagle-import") (part "IND-XFL4020"))
    )
    (comp (ref "R54")
      (value "18.2K")
      (footprint "eagle-import:0603-RES")
      (libsource (lib "eagle-import") (part "RESISTOR0603-RES"))
    )
    (comp (ref "R55")
      (value "300K")
      (footprint "eagle-import:0603-RES")
      (libsource (lib "eagle-import") (part "RESISTOR0603-RES"))
    )
    (comp (ref "R56")
      (value "49.9K")
      (footprint "eagle-import:0603-RES")
      (libsource (lib "eagle-import") (part "RESISTOR0603-RES"))
    )
    (comp (ref "R57")
      (value "1.0M")
      (footprint "eagle-import:0603-RES")
      (libsource (lib "eagle-import") (part "RESISTOR0603-RES"))
    )
    (comp (ref "U7")
      (value "LT8609A")
      (footprint "eagle-import:MSOP-10_MSE")
      (libsource (lib "eagle-import") (part "LT8609A"))
    )
  )
  (nets
    (net (code "1") (name "+3V3") (class "Default")
      (node (ref "C28") (pin "1") (pinfunction "1_1") (pintype "passive"))
      (node (ref "C29") (pin "1") (pinfunction "1_1") (pintype "passive"))
      (node (ref "C30") (pin "1") (pinfunction "1_1") (pintype "passive"))
      (node (ref "C31") (pin "1") (pinfunction "1_1") (pintype "passive"))
      (node (ref "C36") (pin "1") (pinfunction "1_1") (pintype "passive"))
      (node (ref "C37") (pin "1") (pinfunction "1_1") (pintype "passive"))
      (node (ref "R31") (pin "2") (pinfunction "2_2") (pintype "passive"))
      (node (ref "R36") (pin "2") (pinfunction "2_2") (pintype "passive"))
      (node (ref "R37") (pin "2") (pinfunction "2_2") (pintype "passive"))
      (node (ref "U1") (pin "22") (pinfunction "DVCC1_22") (pintype "power_in"))
      (node (ref "U1") (pin "47") (pinfunction "DVCC2_47") (pintype "power_in"))
      (node (ref "U1") (pin "79") (pinfunction "DVCC3_79") (pintype "power_in"))
      (node (ref "U2") (pin "5") (pinfunction "OUT_5") (pintype "bidirectional"))
    )
    (net (code "2") (name "3V3_BUS") (class "Default")
      (node (ref "C69") (pin "2") (pinfunction "2_2") (pintype "passive"))
      (node (ref "C70") (pin "1") (pinfunction "1_1") (pintype "passive"))
      (node (ref "C71") (pin "1") (pinfunction "1_1") (pintype "passive"))
      (node (ref "C76") (pin "2") (pinfunction "2_2") (pintype "passive"))
      (node (ref "C77") (pin "1") (pinfunction "1_1") (pintype "passive"))
      (node (ref "C78") (pin "1") (pinfunction "1_1") (pintype "passive"))
      (node (ref "C83") (pin "2") (pinfunction "2_2") (pintype "passive"))
      (node (ref "C84") (pin "1") (pinfunction "1_1") (pintype "passive"))
      (node (ref "C85") (pin "1") (pinfunction "1_1") (pintype "passive"))
      (node (ref "L7") (pin "2") (pinfunction "2_2") (pintype "bidirectional"))
      (node (ref "L8") (pin "2") (pinfunction "2_2") (pintype "bidirectional"))
      (node (ref "L9") (pin "2") (pinfunction "2_2") (pintype "bidirectional"))
      (node (ref "R52") (pin "2") (pinfunction "2_2") (pintype "passive"))
      (node (ref "R53") (pin "2") (pinfunction "2_2") (pintype "passive"))
      (node (ref "R56") (pin "2") (pinfunction "2_2") (pintype "passive"))
      (node (ref "R57") (pin "2") (pinfunction "2_2") (pintype "passive"))
      (node (ref "R60") (pin "2") (pinfunction "2_2") (pintype "passive"))
      (node (ref "R61") (pin "2") (pinfunction "2_2") (pintype "passive"))
      (node (ref "U14") (pin "2") (pinfunction "VIN1_2") (pintype "bidirectional"))
      (node (ref "U14") (pin "3") (pinfunction "VINS_3") (pintype "bidirectional"))
      (node (ref "U14") (pin "6") (pinfunction "VIN3_6") (pintype "bidirectional"))
      (node (ref "U14") (pin "7") (pinfunction "VIN2_7") (pintype "bidirectional"))
      (node (ref "U15") (pin "2") (pinfunction "VIN1_2") (pintype "bidirectional"))
      (node (ref "U15") (pin "3") (pinfunction "VINS_3") (pintype "bidirectional"))
      (node (ref "U15") (pin "6") (pinfunction "VIN3_6") (pintype "bidirectional"))
      (node (ref "U15") (pin "7") (pinfunction "VIN2_7") (pintype "bidirectional"))
      (node (ref "U16") (pin "2") (pinfunction "VIN1_2") (pintype "bidirectional"))
      (node (ref "U16") (pin "3") (pinfunction "VINS_3") (pintype "bidirectional"))
      (node (ref "U16") (pin "6") (pinfunction "VIN3_6") (pintype "bidirectional"))
      (node (ref "U16") (pin "7") (pinfunction "VIN2_7") (pintype "bidirectional"))
      (node (ref "U17") (pin "2") (pinfunction "VIN1_2") (pintype "bidirectional"))
      (node (ref "U17") (pin "3") (pinfunction "VINS_3") (pintype "bidirectional"))
      (node (ref "U17") (pin "7") (pinfunction "VIN2_7") (pintype "bidirectional"))
      (node (ref "U18") (pin "2") (pinfunction "VIN1_2") (pintype "bidirectional"))
      (node (ref "U18") (pin "3") (pinfunction "VINS_3") (pintype "bidirectional"))
      (node (ref "U18") (pin "7") (pinfunction "VIN2_7") (pintype "bidirectional"))
    )
    (net (code "3") (name "5V_BUS") (class "Default")
      (node (ref "C48") (pin "2") (pinfunction "2_2") (pintype "passive"))
      (node (ref "C49") (pin "1") (pinfunction "1_1") (pintype "passive"))
      (node (ref "C50") (pin "1") (pinfunction "1_1") (pintype "passive"))
      (node (ref "C54") (pin "2") (pinfunction "2_2") (pintype "passive"))
      (node (ref "C55") (pin "1") (pinfunction "1_1") (pintype "passive"))
      (node (ref "C56") (pin "1") (pinfunction "1_1") (pintype "passive"))
      (node (ref "C62") (pin "2") (pinfunction "2_2") (pintype "passive"))
      (node (ref "C63") (pin "1") (pinfunction "1_1") (pintype "passive"))
      (node (ref "C64") (pin "1") (pinfunction "1_1") (pintype "passive"))
      (node (ref "L4") (pin "2") (pinfunction "2_2") (pintype "bidirectional"))
      (node (ref "L5") (pin "2") (pinfunction "2_2") (pintype "bidirectional"))
      (node (ref "L6") (pin "2") (pinfunction "2_2") (pintype "bidirectional"))
      (node (ref "R40") (pin "2") (pinfunction "2_2") (pintype "passive"))
      (node (ref "R41") (pin "2") (pinfunction "2_2") (pintype "passive"))
      (node (ref "R44") (pin "2") (pinfunction "2_2") (pintype "passive"))
      (node (ref "R45") (pin "2") (pinfunction "2_2") (pintype "passive"))
      (node (ref "R48") (pin "2") (pinfunction "2_2") (pintype "passive"))
      (node (ref "R49") (pin "2") (pinfunction "2_2") (pintype "passive"))
      (node (ref "U10") (pin "2") (pinfunction "VIN1_2") (pintype "bidirectional"))
      (node (ref "U10") (pin "3") (pinfunction "VINS_3") (pintype "bidirectional"))
      (node (ref "U10") (pin "6") (pinfunction "VIN3_6") (pintype "bidirectional"))
      (node (ref "U10") (pin "7") (pinfunction "VIN2_7") (pintype "bidirectional"))
      (node (ref "U11") (pin "2") (pinfunction "VIN1_2") (pintype "bidirectional"))
      (node (ref "U11") (pin "3") (pinfunction "VINS_3") (pintype "bidirectional"))
      (node (ref "U11") (pin "6") (pinfunction "VIN3_6") (pintype "bidirectional"))
      (node (ref "U11") (pin "7") (pinfunction "VIN2_7") (pintype "bidirectional"))
      (node (ref "U12") (pin "2") (pinfunction "VIN1_2") (pintype "bidirectional"))
      (node (ref "U12") (pin "3") (pinfunction "VINS_3") (pintype "bidirectional"))
      (node (ref "U12") (pin "7") (pinfunction "VIN2_7") (pintype "bidirectional"))
      (node (ref "U13") (pin "2") (pinfunction "VIN1_2") (pintype "bidirectional"))
      (node (ref "U13") (pin "3") (pinfunction "VINS_3") (pintype "bidirectional"))
      (node (ref "U13") (pin "7") (pinfunction "VIN2_7") (pintype "bidirectional"))
      (node (ref "U9") (pin "2") (pinfunction "VIN1_2") (pintype "bidirectional"))
      (node (ref "U9") (pin "3") (pinfunction "VINS_3") (pintype "bidirectional"))
      (node (ref "U9") (pin "6") (pinfunction "VIN3_6") (pintype "bidirectional"))
      (node (ref "U9") (pin "7") (pinfunction "VIN2_7") (pintype "bidirectional"))
    )
    (net (code "4") (name "BCR1_IN") (class "Default")
      (node (ref "BCR1") (pin "1") (pinfunction "VL_1") (pintype "passive"))
      (node (ref "C7") (pin "2") (pinfunction "2_2") (pintype "passive"))
      (node (ref "C8") (pin "2") (pinfunction "2_2") (pintype "passive"))
      (node (ref "C9") (pin "2") (pinfunction "2_2") (pintype "passive"))
      (node (ref "C97") (pin "1") (pinfunction "1_1") (pintype "passive"))
      (node (ref "J1") (pin "A4") (pinfunction "VBUS_A4") (pintype "power_in"))
      (node (ref "J1") (pin "A9") (pinfunction "VBUS_A9") (pintype "power_in"))
      (node (ref "J1") (pin "B4") (pinfunction "VBUS_B4") (pintype "power_in"))
      (node (ref "J1") (pin "B9") (pinfunction "VBUS_B9") (pintype "power_in"))
      (node (ref "R7") (pin "1") (pinfunction "1_1") (pintype "passive"))
      (node (ref "U19") (pin "3") (pinfunction "D1_3") (pintype "bidirectional"))
      (node (ref "U19") (pin "8") (pinfunction "IN1_8") (pintype "bidirectional"))
    )
    (net (code "5") (name "BCR1_OUT") (class "Default")
      (node (ref "BCR1") (pin "3") (pinfunction "VH_3") (pintype "passive"))
      (node (ref "C5") (pin "1") (pinfunction "1_1") (pintype "passive"))
      (node (ref "C6") (pin "1") (pinfunction "1_1") (pintype "passive"))
    )
    (net (code "6") (name "BCR1_VCC") (class "Default")
      (node (ref "BCR1") (pin "9") (pinfunction "VCC_9") (pintype "power_in"))
      (node (ref "C2") (pin "1") (pinfunction "1_1") (pintype "passive"))
    )
    (net (code "7") (name "BCR1_VLIM") (class "Default")
      (node (ref "BCR1") (pin "18") (pinfunction "VLIM_18") (pintype "passive"))
      (node (ref "R7") (pin "2") (pinfunction "2_2") (pintype "passive"))
      (node (ref "R8") (pin "1") (pinfunction "1_1") (pintype "passive"))
    )
    (net (code "8") (name "BCR2_IN") (class "Default")
      (node (ref "BCR2") (pin "1") (pinfunction "VL_1") (pintype "passive"))
      (node (ref "C16") (pin "2") (pinfunction "2_2") (pintype "passive"))
      (node (ref "C17") (pin "2") (pinfunction "2_2") (pintype "passive"))
      (node (ref "C18") (pin "2") (pinfunction "2_2") (pintype "passive"))
      (node (ref "R17") (pin "1") (pinfunction "1_1") (pintype "passive"))
      (node (ref "U19") (pin "7") (pinfunction "OUT_7") (pintype "bidirectional"))
    )
    (net (code "9") (name "BCR2_OUT") (class "Default")
      (node (ref "BCR2") (pin "3") (pinfunction "VH_3") (pintype "passive"))
      (node (ref "C14") (pin "1") (pinfunction "1_1") (pintype "passive"))
      (node (ref "C15") (pin "1") (pinfunction "1_1") (pintype "passive"))
    )
    (net (code "10") (name "BCR2_VCC") (class "Default")
      (node (ref "BCR2") (pin "9") (pinfunction "VCC_9") (pintype "power_in"))
      (node (ref "C11") (pin "1") (pinfunction "1_1") (pintype "passive"))
      (node (ref "R32") (pin "1") (pinfunction "1_1") (pintype "passive"))
      (node (ref "R33") (pin "1") (pinfunction "1_1") (pintype "passive"))
      (node (ref "R34") (pin "1") (pinfunction "1_1") (pintype "passive"))
      (node (ref "R35") (pin "1") (pinfunction "1_1") (pintype "passive"))
    )
    (net (code "11") (name "BCR2_VLIM") (class "Default")
      (node (ref "BCR2") (pin "18") (pinfunction "VLIM_18") (pintype "passive"))
      (node (ref "R17") (pin "2") (pinfunction "2_2") (pintype "passive"))
      (node (ref "R18") (pin "1") (pinfunction "1_1") (pintype "passive"))
    )
    (net (code "12") (name "BCR3_IN") (class "Default")
      (node (ref "BCR3") (pin "1") (pinfunction "VL_1") (pintype "passive"))
      (node (ref "C25") (pin "2") (pinfunction "2_2") (pintype "passive"))
      (node (ref "C26") (pin "2") (pinfunction "2_2") (pintype "passive"))
      (node (ref "C27") (pin "2") (pinfunction "2_2") (pintype "passive"))
      (node (ref "C98") (pin "1") (pinfunction "1_1") (pintype "passive"))
      (node (ref "J2") (pin "A4") (pinfunction "VBUS_A4") (pintype "power_in"))
      (node (ref "J2") (pin "A9") (pinfunction "VBUS_A9") (pintype "power_in"))
      (node (ref "J2") (pin "B4") (pinfunction "VBUS_B4") (pintype "power_in"))
      (node (ref "J2") (pin "B9") (pinfunction "VBUS_B9") (pintype "power_in"))
      (node (ref "R27") (pin "1") (pinfunction "1_1") (pintype "passive"))
      (node (ref "U19") (pin "6") (pinfunction "IN2_6") (pintype "bidirectional"))
    )
    (net (code "13") (name "BCR3_OUT") (class "Default")
      (node (ref "BCR3") (pin "3") (pinfunction "VH_3") (pintype "passive"))
      (node (ref "C23") (pin "1") (pinfunction "1_1") (pintype "passive"))
      (node (ref "C24") (pin "1") (pinfunction "1_1") (pintype "passive"))
    )
    (net (code "14") (name "BCR3_VCC") (class "Default")
      (node (ref "BCR3") (pin "9") (pinfunction "VCC_9") (pintype "power_in"))
      (node (ref "C20") (pin "1") (pinfunction "1_1") (pintype "passive"))
    )
    (net (code "15") (name "BCR3_VLIM") (class "Default")
      (node (ref "BCR3") (pin "18") (pinfunction "VLIM_18") (pintype "passive"))
      (node (ref "R27") (pin "2") (pinfunction "2_2") (pintype "passive"))
      (node (ref "R28") (pin "1") (pinfunction "1_1") (pintype "passive"))
    )
    (net (code "16") (name "GND") (class "Default")
      (node (ref "BCR1") (pin "12") (pinfunction "MID_12") (pintype "passive"))
      (node (ref "BCR1") (pin "22") (pinfunction "OLIM_22") (pintype "passive"))
      (node (ref "BCR1") (pin "5") (pinfunction "PGND_5") (pintype "passive"))
      (node (ref "BCR2") (pin "12") (pinfunction "MID_12") (pintype "passive"))
      (node (ref "BCR2") (pin "22") (pinfunction "OLIM_22") (pintype "passive"))
      (node (ref "BCR2") (pin "5") (pinfunction "PGND_5") (pintype "passive"))
      (node (ref "BCR3") (pin "12") (pinfunction "MID_12") (pintype "passive"))
      (node (ref "BCR3") (pin "22") (pinfunction "OLIM_22") (pintype "passive"))
      (node (ref "BCR3") (pin "5") (pinfunction "PGND_5") (pintype "passive"))
      (node (ref "C14") (pin "2") (pinfunction "2_2") (pintype "passive"))
      (node (ref "C15") (pin "2") (pinfunction "2_2") (pintype "passive"))
      (node (ref "C16") (pin "1") (pinfunction "1_1") (pintype "passive"))
      (node (ref "C17") (pin "1") (pinfunction "1_1") (pintype "passive"))
      (node (ref "C18") (pin "1") (pinfunction "1_1") (pintype "passive"))
      (node (ref "C23") (pin "2") (pinfunction "2_2") (pintype "passive"))
      (node (ref "C24") (pin "2") (pinfunction "2_2") (pintype "passive"))
      (node (ref "C25") (pin "1") (pinfunction "1_1") (pintype "passive"))
      (node (ref "C26") (pin "1") (pinfunction "1_1") (pintype "passive"))
      (node (ref "C27") (pin "1") (pinfunction "1_1") (pintype "passive"))
      (node (ref "C28") (pin "2") (pinfunction "2_2") (pintype "passive"))
      (node (ref "C29") (pin "2") (pinfunction "2_2") (pintype "passive"))
      (node (ref "C30") (pin "2") (pinfunction "2_2") (pintype "passive"))
      (node (ref "C31") (pin "2") (pinfunction "2_2") (pintype "passive"))
      (node (ref "C32") (pin "1") (pinfunction "1_1") (pintype "passive"))
      (node (ref "C33") (pin "2") (pinfunction "2_2") (pintype "passive"))
      (node (ref "C34") (pin "1") (pinfunction "1_1") (pintype "passive"))
      (node (ref "C35") (pin "2") (pinfunction "2_2") (pintype "passive"))
      (node (ref "C36") (pin "2") (pinfunction "2_2") (pintype "passive"))
      (node (ref "C37") (pin "2") (pinfunction "2_2") (pintype "passive"))
      (node (ref "C38") (pin "2") (pinfunction "2_2") (pintype "passive"))
      (node (ref "C39") (pin "2") (pinfunction "2_2") (pintype "passive"))
      (node (ref "C40") (pin "2") (pinfunction "2_2") (pintype "passive"))
      (node (ref "C41") (pin "2") (pinfunction "2_2") (pintype "passive"))
      (node (ref "C42") (pin "2") (pinfunction "2_2") (pintype "passive"))
      (node (ref "C43") (pin "2") (pinfunction "2_2") (pintype "passive"))
      (node (ref "C44") (pin "2") (pinfunction "2_2") (pintype "passive"))
      (node (ref "C45") (pin "2") (pinfunction "2_2") (pintype "passive"))
      (node (ref "C46") (pin "2") (pinfunction "2_2") (pintype "passive"))
      (node (ref "C49") (pin "2") (pinfunction "2_2") (pintype "passive"))
      (node (ref "C5") (pin "2") (pinfunction "2_2") (pintype "passive"))
      (node (ref "C50") (pin "2") (pinfunction "2_2") (pintype "passive"))
      (node (ref "C51") (pin "2") (pinfunction "2_2") (pintype "passive"))
      (node (ref "C52") (pin "2") (pinfunction "2_2") (pintype "passive"))
      (node (ref "C55") (pin "2") (pinfunction "2_2") (pintype "passive"))
      (node (ref "C56") (pin "2") (pinfunction "2_2") (pintype "passive"))
      (node (ref "C57") (pin "2") (pinfunction "2_2") (pintype "passive"))
      (node (ref "C58") (pin "2") (pinfunction "2_2") (pintype "passive"))
      (node (ref "C59") (pin "2") (pinfunction "2_2") (pintype "passive"))
      (node (ref "C6") (pin "2") (pinfunction "2_2") (pintype "passive"))
      (node (ref "C60") (pin "2") (pinfunction "2_2") (pintype "passive"))
      (node (ref "C63") (pin "2") (pinfunction "2_2") (pintype "passive"))
      (node (ref "C64") (pin "2") (pinfunction "2_2") (pintype "passive"))
      (node (ref "C65") (pin "2") (pinfunction "2_2") (pintype "passive"))
      (node (ref "C66") (pin "2") (pinfunction "2_2") (pintype "passive"))
      (node (ref "C67") (pin "2") (pinfunction "2_2") (pintype "passive"))
      (node (ref "C7") (pin "1") (pinfunction "1_1") (pintype "passive"))
      (node (ref "C70") (pin "2") (pinfunction "2_2") (pintype "passive"))
      (node (ref "C71") (pin "2") (pinfunction "2_2") (pintype "passive"))
      (node (ref "C72") (pin "2") (pinfunction "2_2") (pintype "passive"))
      (node (ref "C73") (pin "2") (pinfunction "2_2") (pintype "passive"))
      (node (ref "C74") (pin "2") (pinfunction "2_2") (pintype "passive"))
      (node (ref "C77") (pin "2") (pinfunction "2_2") (pintype "passive"))
      (node (ref "C78") (pin "2") (pinfunction "2_2") (pintype "passive"))
      (node (ref "C79") (pin "2") (pinfunction "2_2") (pintype "passive"))
      (node (ref "C8") (pin "1") (pinfunction "1_1") (pintype "passive"))
      (node (ref "C80") (pin "2") (pinfunction "2_2") (pintype "passive"))
      (node (ref "C81") (pin "2") (pinfunction "2_2") (pintype "passive"))
      (node (ref "C84") (pin "2") (pinfunction "2_2") (pintype "passive"))
      (node (ref "C85") (pin "2") (pinfunction "2_2") (pintype "passive"))
      (node (ref "C86") (pin "2") (pinfunction "2_2") (pintype "passive"))
      (node (ref "C87") (pin "2") (pinfunction "2_2") (pintype "passive"))
      (node (ref "C88") (pin "2") (pinfunction "2_2") (pintype "passive"))
      (node (ref "C89") (pin "2") (pinfunction "2_2") (pintype "passive"))
      (node (ref "C9") (pin "1") (pinfunction "1_1") (pintype "passive"))
      (node (ref "C90") (pin "2") (pinfunction "2_2") (pintype "passive"))
      (node (ref "C91") (pin "2") (pinfunction "2_2") (pintype "passive"))
      (node (ref "C92") (pin "2") (pinfunction "2_2") (pintype "passive"))
      (node (ref "C93") (pin "2") (pinfunction "2_2") (pintype "passive"))
      (node (ref "C94") (pin "2") (pinfunction "2_2") (pintype "passive"))
      (node (ref "C95") (pin "2") (pinfunction "2_2") (pintype "passive"))
      (node (ref "C96") (pin "2") (pinfunction "2_2") (pintype "passive"))
      (node (ref "C97") (pin "2") (pinfunction "2_2") (pintype "passive"))
      (node (ref "C98") (pin "2") (pinfunction "2_2") (pintype "passive"))
      (node (ref "D1") (pin "2") (pinfunction "1_2") (pintype "bidirectional"))
      (node (ref "D2") (pin "2") (pinfunction "1_2") (pintype "bidirectional"))
      (node (ref "D3") (pin "2") (pinfunction "1_2") (pintype "bidirectional"))
      (node (ref "J1") (pin "A1") (pinfunction "GND_A1") (pintype "power_in"))
      (node (ref "J1") (pin "A12") (pinfunction "GND_A12") (pintype "power_in"))
      (node (ref "J1") (pin "B1") (pinfunction "GND_B1") (pintype "power_in"))
      (node (ref "J1") (pin "B12") (pinfunction "GND_B12") (pintype "power_in"))
      (node (ref "J1") (pin "SH1") (pinfunction "SHIELD_SH1") (pintype "power_in"))
      (node (ref "J1") (pin "SH2") (pinfunction "SHIELD_SH2") (pintype "power_in"))
      (node (ref "J1") (pin "SH3") (pinfunction "SHIELD_SH3") (pintype "power_in"))
      (node (ref "J1") (pin "SH4") (pinfunction "SHIELD_SH4") (pintype "power_in"))
      (node (ref "J1") (pin "SH5") (pinfunction "SHIELD_SH5") (pintype "power_in"))
      (node (ref "J1") (pin "SH6") (pinfunction "SHIELD_SH6") (pintype "power_in"))
      (node (ref "J2") (pin "A1") (pinfunction "GND_A1") (pintype "power_in"))
      (node (ref "J2") (pin "A12") (pinfunction "GND_A12") (pintype "power_in"))
      (node (ref "J2") (pin "B1") (pinfunction "GND_B1") (pintype "power_in"))
      (node (ref "J2") (pin "B12") (pinfunction "GND_B12") (pintype "power_in"))
      (node (ref "J2") (pin "SH1") (pinfunction "SHIELD_SH1") (pintype "power_in"))
      (node (ref "J2") (pin "SH2") (pinfunction "SHIELD_SH2") (pintype "power_in"))
      (node (ref "J2") (pin "SH3") (pinfunction "SHIELD_SH3") (pintype "power_in"))
      (node (ref "J2") (pin "SH4") (pinfunction "SHIELD_SH4") (pintype "power_in"))
      (node (ref "J2") (pin "SH5") (pinfunction "SHIELD_SH5") (pintype "power_in"))
      (node (ref "J2") (pin "SH6") (pinfunction "SHIELD_SH6") (pintype "power_in"))
      (node (ref "R10") (pin "1") (pinfunction "1_1") (pintype "passive"))
      (node (ref "R19") (pin "1") (pinfunction "1_1") (pintype "passive"))
      (node (ref "R20") (pin "1") (pinfunction "1_1") (pintype "passive"))
      (node (ref "R29") (pin "1") (pinfunction "1_1") (pintype "passive"))
      (node (ref "R30") (pin "1") (pinfunction "1_1") (pintype "passive"))
      (node (ref "R38") (pin "1") (pinfunction "1_1") (pintype "passive"))
      (node (ref "R39") (pin "1") (pinfunction "1_1") (pintype "passive"))
      (node (ref "R42") (pin "1") (pinfunction "1_1") (pintype "passive"))
      (node (ref "R43") (pin "1") (pinfunction "1_1") (pintype "passive"))
      (node (ref "R46") (pin "1") (pinfunction "1_1") (pintype "passive"))
      (node (ref "R47") (pin "1") (pinfunction "1_1") (pintype "passive"))
      (node (ref "R50") (pin "1") (pinfunction "1_1") (pintype "passive"))
      (node (ref "R51") (pin "1") (pinfunction "1_1") (pintype "passive"))
      (node (ref "R54") (pin "1") (pinfunction "1_1") (pintype "passive"))
      (node (ref "R55") (pin "1") (pinfunction "1_1") (pintype "passive"))
      (node (ref "R58") (pin "1") (pinfunction "1_1") (pintype "passive"))
      (node (ref "R59") (pin "1") (pinfunction "1_1") (pintype "passive"))
      (node (ref "R62") (pin "2") (pinfunction "2_2") (pintype "passive"))
      (node (ref "R63") (pin "2") (pinfunction "2_2") (pintype "passive"))
      (node (ref "R64") (pin "2") (pinfunction "2_2") (pintype "passive"))
      (node (ref "R65") (pin "2") (pinfunction "2_2") (pintype "passive"))
      (node (ref "R66") (pin "1") (pinfunction "1_1") (pintype "passive"))
      (node (ref "R9") (pin "1") (pinfunction "1_1") (pintype "passive"))
      (node (ref "U1") (pin "21") (pinfunction "DVSS1_21") (pintype "power_in"))
      (node (ref "U1") (pin "46") (pinfunction "DVSS2_46") (pintype "power_in"))
      (node (ref "U1") (pin "65") (pinfunction "AVSS3_65") (pintype "power_in"))
      (node (ref "U1") (pin "68") (pinfunction "AVSS1_68") (pintype "power_in"))
      (node (ref "U1") (pin "71") (pinfunction "AVSS2_71") (pintype "power_in"))
      (node (ref "U1") (pin "78") (pinfunction "DVSS3_78") (pintype "power_in"))
      (node (ref "U10") (pin "5") (pinfunction "GND_5") (pintype "bidirectional"))
      (node (ref "U11") (pin "5") (pinfunction "GND_5") (pintype "bidirectional"))
      (node (ref "U12") (pin "5") (pinfunction "GND_5") (pintype "bidirectional"))
      (node (ref "U13") (pin "5") (pinfunction "GND_5") (pintype "bidirectional"))
      (node (ref "U14") (pin "5") (pinfunction "GND_5") (pintype "bidirectional"))
      (node (ref "U15") (pin "5") (pinfunction "GND_5") (pintype "bidirectional"))
      (node (ref "U16") (pin "5") (pinfunction "GND_5") (pintype "bidirectional"))
      (node (ref "U17") (pin "5") (pinfunction "GND_5") (pintype "bidirectional"))
      (node (ref "U18") (pin "5") (pinfunction "GND_5") (pintype "bidirectional"))
      (node (ref "U19") (pin "2") (pinfunction "D0_2") (pintype "bidirectional"))
      (node (ref "U19") (pin "5") (pinfunction "GND_5") (pintype "bidirectional"))
      (node (ref "U2") (pin "2") (pinfunction "GND_2") (pintype "bidirectional"))
      (node (ref "U3") (pin "11") (pinfunction "GND_11") (pintype "bidirectional"))
      (node (ref "U3") (pin "5") (pinfunction "SYNC_5") (pintype "bidirectional"))
      (node (ref "U4") (pin "11") (pinfunction "GND_11") (pintype "bidirectional"))
      (node (ref "U4") (pin "5") (pinfunction "SYNC_5") (pintype "bidirectional"))
      (node (ref "U5") (pin "11") (pinfunction "GND_11") (pintype "bidirectional"))
      (node (ref "U5") (pin "5") (pinfunction "SYNC_5") (pintype "bidirectional"))
      (node (ref "U6") (pin "11") (pinfunction "GND_11") (pintype "bidirectional"))
      (node (ref "U6") (pin "5") (pinfunction "SYNC_5") (pintype "bidirectional"))
      (node (ref "U7") (pin "11") (pinfunction "GND_11") (pintype "bidirectional"))
      (node (ref "U7") (pin "5") (pinfunction "SYNC_5") (pintype "bidirectional"))
      (node (ref "U8") (pin "11") (pinfunction "GND_11") (pintype "bidirectional"))
      (node (ref "U8") (pin "5") (pinfunction "SYNC_5") (pintype "bidirectional"))
      (node (ref "U9") (pin "5") (pinfunction "GND_5") (pintype "bidirectional"))
      (node (ref "X1") (pin "3") (pinfunction "P$3_3") (pintype "bidirectional"))
    )
    (net (code "17") (name "GNDA1") (class "Default")
      (node (ref "BCR1") (pin "10") (pinfunction "AGND_10") (pintype "passive"))
      (node (ref "BCR1") (pin "13") (pinfunction "LED1_13") (pintype "bidirectional"))
      (node (ref "BCR1") (pin "14") (pinfunction "LED2_14") (pintype "bidirectional"))
      (node (ref "BCR1") (pin "15") (pinfunction "LED3_15") (pintype "bidirectional"))
      (node (ref "BCR1") (pin "16") (pinfunction "LED4_16") (pintype "bidirectional"))
      (node (ref "BCR1") (pin "17") (pinfunction "FB_17") (pintype "passive"))
      (node (ref "BCR1") (pin "8") (pinfunction "MODE_8") (pintype "passive"))
      (node (ref "C1") (pin "1") (pinfunction "1_1") (pintype "passive"))
      (node (ref "C2") (pin "2") (pinfunction "2_2") (pintype "passive"))
      (node (ref "C3") (pin "2") (pinfunction "2_2") (pintype "passive"))
      (node (ref "R1") (pin "2") (pinfunction "2_2") (pintype "passive"))
      (node (ref "R10") (pin "2") (pinfunction "2_2") (pintype "passive"))
      (node (ref "R2") (pin "2") (pinfunction "2_2") (pintype "passive"))
      (node (ref "R4") (pin "2") (pinfunction "2_2") (pintype "passive"))
      (node (ref "R5") (pin "2") (pinfunction "2_2") (pintype "passive"))
      (node (ref "R8") (pin "2") (pinfunction "2_2") (pintype "passive"))
      (node (ref "R9") (pin "2") (pinfunction "2_2") (pintype "passive"))
    )
    (net (code "18") (name "GNDA2") (class "Default")
      (node (ref "BCR2") (pin "10") (pinfunction "AGND_10") (pintype "passive"))
      (node (ref "BCR2") (pin "17") (pinfunction "FB_17") (pintype "passive"))
      (node (ref "BCR2") (pin "8") (pinfunction "MODE_8") (pintype "passive"))
      (node (ref "C10") (pin "1") (pinfunction "1_1") (pintype "passive"))
      (node (ref "C11") (pin "2") (pinfunction "2_2") (pintype "passive"))
      (node (ref "C12") (pin "2") (pinfunction "2_2") (pintype "passive"))
      (node (ref "R11") (pin "2") (pinfunction "2_2") (pintype "passive"))
      (node (ref "R12") (pin "2") (pinfunction "2_2") (pintype "passive"))
      (node (ref "R14") (pin "2") (pinfunction "2_2") (pintype "passive"))
      (node (ref "R15") (pin "2") (pinfunction "2_2") (pintype "passive"))
      (node (ref "R18") (pin "2") (pinfunction "2_2") (pintype "passive"))
      (node (ref "R19") (pin "2") (pinfunction "2_2") (pintype "passive"))
      (node (ref "R20") (pin "2") (pinfunction "2_2") (pintype "passive"))
    )
    (net (code "19") (name "GNDA3") (class "Default")
      (node (ref "BCR3") (pin "10") (pinfunction "AGND_10") (pintype "passive"))
      (node (ref "BCR3") (pin "13") (pinfunction "LED1_13") (pintype "bidirectional"))
      (node (ref "BCR3") (pin "14") (pinfunction "LED2_14") (pintype "bidirectional"))
      (node (ref "BCR3") (pin "15") (pinfunction "LED3_15") (pintype "bidirectional"))
      (node (ref "BCR3") (pin "16") (pinfunction "LED4_16") (pintype "bidirectional"))
      (node (ref "BCR3") (pin "17") (pinfunction "FB_17") (pintype "passive"))
      (node (ref "BCR3") (pin "8") (pinfunction "MODE_8") (pintype "passive"))
      (node (ref "C19") (pin "1") (pinfunction "1_1") (pintype "passive"))
      (node (ref "C20") (pin "2") (pinfunction "2_2") (pintype "passive"))
      (node (ref "C21") (pin "2") (pinfunction "2_2") (pintype "passive"))
      (node (ref "R21") (pin "2") (pinfunction "2_2") (pintype "passive"))
      (node (ref "R22") (pin "2") (pinfunction "2_2") (pintype "passive"))
      (node (ref "R24") (pin "2") (pinfunction "2_2") (pintype "passive"))
      (node (ref "R25") (pin "2") (pinfunction "2_2") (pintype "passive"))
      (node (ref "R28") (pin "2") (pinfunction "2_2") (pintype "passive"))
      (node (ref "R29") (pin "2") (pinfunction "2_2") (pintype "passive"))
      (node (ref "R30") (pin "2") (pinfunction "2_2") (pintype "passive"))
    )
    (net (code "20") (name "Net-(BCR1-BST)") (class "Default")
      (node (ref "BCR1") (pin "6") (pinfunction "BST_6") (pintype "passive"))
      (node (ref "C4") (pin "2") (pinfunction "2_2") (pintype "passive"))
    )
    (net (code "21") (name "Net-(BCR1-IB)") (class "Default")
      (node (ref "BCR1") (pin "21") (pinfunction "IB_21") (pintype "passive"))
      (node (ref "R2") (pin "1") (pinfunction "1_1") (pintype "passive"))
      (node (ref "R3") (pin "1") (pinfunction "1_1") (pintype "passive"))
    )
    (net (code "22") (name "Net-(BCR1-ILIM)") (class "Default")
      (node (ref "BCR1") (pin "24") (pinfunction "ILIM_24") (pintype "passive"))
      (node (ref "R4") (pin "1") (pinfunction "1_1") (pintype "passive"))
    )
    (net (code "23") (name "Net-(BCR1-ISET)") (class "Default")
      (node (ref "BCR1") (pin "23") (pinfunction "ISET_23") (pintype "passive"))
      (node (ref "R1") (pin "1") (pinfunction "1_1") (pintype "passive"))
    )
    (net (code "24") (name "Net-(BCR1-LX)") (class "Default")
      (node (ref "BCR1") (pin "2") (pinfunction "LX_2") (pintype "passive"))
      (node (ref "D1") (pin "1") (pinfunction "2_1") (pintype "bidirectional"))
      (node (ref "L1") (pin "1") (pinfunction "1_1") (pintype "bidirectional"))
    )
    (net (code "25") (name "Net-(BCR1-NTC)") (class "Default")
      (node (ref "BCR1") (pin "20") (pinfunction "NTC_20") (pintype "passive"))
      (node (ref "R5") (pin "1") (pinfunction "1_1") (pintype "passive"))
      (node (ref "R6") (pin "2") (pinfunction "2_2") (pintype "passive"))
    )
    (net (code "26") (name "Net-(BCR1-SW)") (class "Default")
      (node (ref "BCR1") (pin "4") (pinfunction "SW_4") (pintype "passive"))
      (node (ref "C4") (pin "1") (pinfunction "1_1") (pintype "passive"))
      (node (ref "L1") (pin "2") (pinfunction "2_2") (pintype "bidirectional"))
    )
    (net (code "27") (name "Net-(BCR1-TMR)") (class "Default")
      (node (ref "BCR1") (pin "11") (pinfunction "TMR_11") (pintype "passive"))
      (node (ref "C3") (pin "1") (pinfunction "1_1") (pintype "passive"))
    )
    (net (code "28") (name "Net-(BCR1-VNTC)") (class "Default")
      (node (ref "BCR1") (pin "19") (pinfunction "VNTC_19") (pintype "passive"))
      (node (ref "R6") (pin "1") (pinfunction "1_1") (pintype "passive"))
    )
    (net (code "29") (name "Net-(BCR2-BST)") (class "Default")
      (node (ref "BCR2") (pin "6") (pinfunction "BST_6") (pintype "passive"))
      (node (ref "C13") (pin "2") (pinfunction "2_2") (pintype "passive"))
    )
    (net (code "30") (name "Net-(BCR2-IB)") (class "Default")
      (node (ref "BCR2") (pin "21") (pinfunction "IB_21") (pintype "passive"))
      (node (ref "R12") (pin "1") (pinfunction "1_1") (pintype "passive"))
      (node (ref "R13") (pin "1") (pinfunction "1_1") (pintype "passive"))
    )
    (net (code "31") (name "Net-(BCR2-ILIM)") (class "Default")
      (node (ref "BCR2") (pin "24") (pinfunction "ILIM_24") (pintype "passive"))
      (node (ref "R14") (pin "1") (pinfunction "1_1") (pintype "passive"))
    )
    (net (code "32") (name "Net-(BCR2-ISET)") (class "Default")
      (node (ref "BCR2") (pin "23") (pinfunction "ISET_23") (pintype "passive"))
      (node (ref "R11") (pin "1") (pinfunction "1_1") (pintype "passive"))
    )
    (net (code "33") (name "Net-(BCR2-LED1)") (class "Default")
      (node (ref "BCR2") (pin "13") (pinfunction "LED1_13") (pintype "bidirectional"))
      (node (ref "LED1") (pin "2") (pinfunction "2_2") (pintype "bidirectional"))
    )
    (net (code "34") (name "Net-(BCR2-LED2)") (class "Default")
      (node (ref "BCR2") (pin "14") (pinfunction "LED2_14") (pintype "bidirectional"))
      (node (ref "LED2") (pin "2") (pinfunction "2_2") (pintype "bidirectional"))
    )
    (net (code "35") (name "Net-(BCR2-LED3)") (class "Default")
      (node (ref "BCR2") (pin "15") (pinfunction "LED3_15") (pintype "bidirectional"))
      (node (ref "LED3") (pin "2") (pinfunction "2_2") (pintype "bidirectional"))
    )
    (net (code "36") (name "Net-(BCR2-LED4)") (class "Default")
      (node (ref "BCR2") (pin "16") (pinfunction "LED4_16") (pintype "bidirectional"))
      (node (ref "LED4") (pin "2") (pinfunction "2_2") (pintype "bidirectional"))
    )
    (net (code "37") (name "Net-(BCR2-LX)") (class "Default")
      (node (ref "BCR2") (pin "2") (pinfunction "LX_2") (pintype "passive"))
      (node (ref "D2") (pin "1") (pinfunction "2_1") (pintype "bidirectional"))
      (node (ref "L2") (pin "1") (pinfunction "1_1") (pintype "bidirectional"))
    )
    (net (code "38") (name "Net-(BCR2-NTC)") (class "Default")
      (node (ref "BCR2") (pin "20") (pinfunction "NTC_20") (pintype "passive"))
      (node (ref "R15") (pin "1") (pinfunction "1_1") (pintype "passive"))
      (node (ref "R16") (pin "2") (pinfunction "2_2") (pintype "passive"))
    )
    (net (code "39") (name "Net-(BCR2-SW)") (class "Default")
      (node (ref "BCR2") (pin "4") (pinfunction "SW_4") (pintype "passive"))
      (node (ref "C13") (pin "1") (pinfunction "1_1") (pintype "passive"))
      (node (ref "L2") (pin "2") (pinfunction "2_2") (pintype "bidirectional"))
    )
    (net (code "40") (name "Net-(BCR2-TMR)") (class "Default")
      (node (ref "BCR2") (pin "11") (pinfunction "TMR_11") (pintype "passive"))
      (node (ref "C12") (pin "1") (pinfunction "1_1") (pintype "passive"))
    )
    (net (code "41") (name "Net-(BCR2-VNTC)") (class "Default")
      (node (ref "BCR2") (pin "19") (pinfunction "VNTC_19") (pintype "passive"))
      (node (ref "R16") (pin "1") (pinfunction "1_1") (pintype "passive"))
    )
    (net (code "42") (name "Net-(BCR3-BST)") (class "Default")
      (node (ref "BCR3") (pin "6") (pinfunction "BST_6") (pintype "passive"))
      (node (ref "C22") (pin "2") (pinfunction "2_2") (pintype "passive"))
    )
    (net (code "43") (name "Net-(BCR3-IB)") (class "Default")
      (node (ref "BCR3") (pin "21") (pinfunction "IB_21") (pintype "passive"))
      (node (ref "R22") (pin "1") (pinfunction "1_1") (pintype "passive"))
      (node (ref "R23") (pin "1") (pinfunction "1_1") (pintype "passive"))
    )
    (net (code "44") (name "Net-(BCR3-ILIM)") (class "Default")
      (node (ref "BCR3") (pin "24") (pinfunction "ILIM_24") (pintype "passive"))
      (node (ref "R24") (pin "1") (pinfunction "1_1") (pintype "passive"))
    )
    (net (code "45") (name "Net-(BCR3-ISET)") (class "Default")
      (node (ref "BCR3") (pin "23") (pinfunction "ISET_23") (pintype "passive"))
      (node (ref "R21") (pin "1") (pinfunction "1_1") (pintype "passive"))
    )
    (net (code "46") (name "Net-(BCR3-LX)") (class "Default")
      (node (ref "BCR3") (pin "2") (pinfunction "LX_2") (pintype "passive"))
      (node (ref "D3") (pin "1") (pinfunction "2_1") (pintype "bidirectional"))
      (node (ref "L3") (pin "1") (pinfunction "1_1") (pintype "bidirectional"))
    )
    (net (code "47") (name "Net-(BCR3-NTC)") (class "Default")
      (node (ref "BCR3") (pin "20") (pinfunction "NTC_20") (pintype "passive"))
      (node (ref "R25") (pin "1") (pinfunction "1_1") (pintype "passive"))
      (node (ref "R26") (pin "2") (pinfunction "2_2") (pintype "passive"))
    )
    (net (code "48") (name "Net-(BCR3-SW)") (class "Default")
      (node (ref "BCR3") (pin "4") (pinfunction "SW_4") (pintype "passive"))
      (node (ref "C22") (pin "1") (pinfunction "1_1") (pintype "passive"))
      (node (ref "L3") (pin "2") (pinfunction "2_2") (pintype "bidirectional"))
    )
    (net (code "49") (name "Net-(BCR3-TMR)") (class "Default")
      (node (ref "BCR3") (pin "11") (pinfunction "TMR_11") (pintype "passive"))
      (node (ref "C21") (pin "1") (pinfunction "1_1") (pintype "passive"))
    )
    (net (code "50") (name "Net-(BCR3-VNTC)") (class "Default")
      (node (ref "BCR3") (pin "19") (pinfunction "VNTC_19") (pintype "passive"))
      (node (ref "R26") (pin "1") (pinfunction "1_1") (pintype "passive"))
    )
    (net (code "51") (name "Net-(C1-Pad2)") (class "Default")
      (node (ref "C1") (pin "2") (pinfunction "2_2") (pintype "passive"))
      (node (ref "R3") (pin "2") (pinfunction "2_2") (pintype "passive"))
    )
    (net (code "52") (name "Net-(C10-Pad2)") (class "Default")
      (node (ref "C10") (pin "2") (pinfunction "2_2") (pintype "passive"))
      (node (ref "R13") (pin "2") (pinfunction "2_2") (pintype "passive"))
    )
    (net (code "53") (name "Net-(C19-Pad2)") (class "Default")
      (node (ref "C19") (pin "2") (pinfunction "2_2") (pintype "passive"))
      (node (ref "R23") (pin "2") (pinfunction "2_2") (pintype "passive"))
    )
    (net (code "54") (name "Net-(J1-CC1)") (class "Default")
      (node (ref "J1") (pin "A5") (pinfunction "CC1_A5") (pintype "bidirectional"))
      (node (ref "R62") (pin "1") (pinfunction "1_1") (pintype "passive"))
    )
    (net (code "55") (name "Net-(J1-CC2)") (class "Default")
      (node (ref "J1") (pin "B5") (pinfunction "CC2_B5") (pintype "bidirectional"))
      (node (ref "R63") (pin "1") (pinfunction "1_1") (pintype "passive"))
    )
    (net (code "56") (name "Net-(J1-DN1)") (class "Default")
      (node (ref "J1") (pin "A7") (pinfunction "DN1_A7") (pintype "bidirectional"))
      (node (ref "J1") (pin "B7") (pinfunction "DN2_B7") (pintype "bidirectional"))
    )
    (net (code "57") (name "Net-(J1-DP1)") (class "Default")
      (node (ref "J1") (pin "A6") (pinfunction "DP1_A6") (pintype "bidirectional"))
      (node (ref "J1") (pin "B6") (pinfunction "DP2_B6") (pintype "bidirectional"))
    )
    (net (code "58") (name "Net-(J2-CC1)") (class "Default")
      (node (ref "J2") (pin "A5") (pinfunction "CC1_A5") (pintype "bidirectional"))
      (node (ref "R64") (pin "1") (pinfunction "1_1") (pintype "passive"))
    )
    (net (code "59") (name "Net-(J2-CC2)") (class "Default")
      (node (ref "J2") (pin "B5") (pinfunction "CC2_B5") (pintype "bidirectional"))
      (node (ref "R65") (pin "1") (pinfunction "1_1") (pintype "passive"))
    )
    (net (code "60") (name "Net-(J2-DN1)") (class "Default")
      (node (ref "J2") (pin "A7") (pinfunction "DN1_A7") (pintype "bidirectional"))
      (node (ref "J2") (pin "B7") (pinfunction "DN2_B7") (pintype "bidirectional"))
    )
    (net (code "61") (name "Net-(J2-DP1)") (class "Default")
      (node (ref "J2") (pin "A6") (pinfunction "DP1_A6") (pintype "bidirectional"))
      (node (ref "J2") (pin "B6") (pinfunction "DP2_B6") (pintype "bidirectional"))
    )
    (net (code "62") (name "Net-(LED1-Pad1)") (class "Default")
      (node (ref "LED1") (pin "1") (pinfunction "1_1") (pintype "bidirectional"))
      (node (ref "R32") (pin "2") (pinfunction "2_2") (pintype "passive"))
    )
    (net (code "63") (name "Net-(LED2-Pad1)") (class "Default")
      (node (ref "LED2") (pin "1") (pinfunction "1_1") (pintype "bidirectional"))
      (node (ref "R33") (pin "2") (pinfunction "2_2") (pintype "passive"))
    )
    (net (code "64") (name "Net-(LED3-Pad1)") (class "Default")
      (node (ref "LED3") (pin "1") (pinfunction "1_1") (pintype "bidirectional"))
      (node (ref "R34") (pin "2") (pinfunction "2_2") (pintype "passive"))
    )
    (net (code "65") (name "Net-(LED4-Pad1)") (class "Default")
      (node (ref "LED4") (pin "1") (pinfunction "1_1") (pintype "bidirectional"))
      (node (ref "R35") (pin "2") (pinfunction "2_2") (pintype "passive"))
    )
    (net (code "66") (name "Net-(U1-AVCC1)") (class "Default")
      (node (ref "C32") (pin "2") (pinfunction "2_2") (pintype "passive"))
      (node (ref "R31") (pin "1") (pinfunction "1_1") (pintype "passive"))
      (node (ref "U1") (pin "64") (pinfunction "AVCC1_64") (pintype "power_in"))
    )
    (net (code "67") (name "Net-(U2-BYP)") (class "Default")
      (node (ref "C38") (pin "1") (pinfunction "1_1") (pintype "passive"))
      (node (ref "U2") (pin "4") (pinfunction "BYP_4") (pintype "bidirectional"))
    )
    (net (code "68") (name "Net-(U3-BST)") (class "Default")
      (node (ref "C47") (pin "1") (pinfunction "1_1") (pintype "passive"))
      (node (ref "U3") (pin "1") (pinfunction "BST_1") (pintype "bidirectional"))
    )
    (net (code "69") (name "Net-(U3-FB)") (class "Default")
      (node (ref "C48") (pin "1") (pinfunction "1_1") (pintype "passive"))
      (node (ref "R39") (pin "2") (pinfunction "2_2") (pintype "passive"))
      (node (ref "R41") (pin "1") (pinfunction "1_1") (pintype "passive"))
      (node (ref "U3") (pin "6") (pinfunction "FB_6") (pintype "bidirectional"))
    )
    (net (code "70") (name "Net-(U3-INTVCC)") (class "Default")
      (node (ref "C46") (pin "1") (pinfunction "1_1") (pintype "passive"))
      (node (ref "U3") (pin "3") (pinfunction "INTVCC_3") (pintype "bidirectional"))
    )
    (net (code "71") (name "Net-(U3-PG)") (class "Default")
      (node (ref "R40") (pin "1") (pinfunction "1_1") (pintype "passive"))
      (node (ref "U3") (pin "8") (pinfunction "PG_8") (pintype "bidirectional"))
    )
    (net (code "72") (name "Net-(U3-RT)") (class "Default")
      (node (ref "R38") (pin "2") (pinfunction "2_2") (pintype "passive"))
      (node (ref "U3") (pin "4") (pinfunction "RT_4") (pintype "bidirectional"))
    )
    (net (code "73") (name "Net-(U3-SW)") (class "Default")
      (node (ref "C47") (pin "2") (pinfunction "2_2") (pintype "passive"))
      (node (ref "L4") (pin "1") (pinfunction "1_1") (pintype "bidirectional"))
      (node (ref "U3") (pin "2") (pinfunction "SW_2") (pintype "bidirectional"))
    )
    (net (code "74") (name "Net-(U3-TRSS)") (class "Default")
      (node (ref "C45") (pin "1") (pinfunction "1_1") (pintype "passive"))
      (node (ref "U3") (pin "7") (pinfunction "TRSS_7") (pintype "bidirectional"))
    )
    (net (code "75") (name "Net-(U4-BST)") (class "Default")
      (node (ref "C53") (pin "1") (pinfunction "1_1") (pintype "passive"))
      (node (ref "U4") (pin "1") (pinfunction "BST_1") (pintype "bidirectional"))
    )
    (net (code "76") (name "Net-(U4-FB)") (class "Default")
      (node (ref "C54") (pin "1") (pinfunction "1_1") (pintype "passive"))
      (node (ref "R43") (pin "2") (pinfunction "2_2") (pintype "passive"))
      (node (ref "R45") (pin "1") (pinfunction "1_1") (pintype "passive"))
      (node (ref "U4") (pin "6") (pinfunction "FB_6") (pintype "bidirectional"))
    )
    (net (code "77") (name "Net-(U4-INTVCC)") (class "Default")
      (node (ref "C52") (pin "1") (pinfunction "1_1") (pintype "passive"))
      (node (ref "U4") (pin "3") (pinfunction "INTVCC_3") (pintype "bidirectional"))
    )
    (net (code "78") (name "Net-(U4-PG)") (class "Default")
      (node (ref "R44") (pin "1") (pinfunction "1_1") (pintype "passive"))
      (node (ref "U4") (pin "8") (pinfunction "PG_8") (pintype "bidirectional"))
    )
    (net (code "79") (name "Net-(U4-RT)") (class "Default")
      (node (ref "R42") (pin "2") (pinfunction "2_2") (pintype "passive"))
      (node (ref "U4") (pin "4") (pinfunction "RT_4") (pintype "bidirectional"))
    )
    (net (code "80") (name "Net-(U4-SW)") (class "Default")
      (node (ref "C53") (pin "2") (pinfunction "2_2") (pintype "passive"))
      (node (ref "L5") (pin "1") (pinfunction "1_1") (pintype "bidirectional"))
      (node (ref "U4") (pin "2") (pinfunction "SW_2") (pintype "bidirectional"))
    )
    (net (code "81") (name "Net-(U4-TRSS)") (class "Default")
      (node (ref "C51") (pin "1") (pinfunction "1_1") (pintype "passive"))
      (node (ref "U4") (pin "7") (pinfunction "TRSS_7") (pintype "bidirectional"))
    )
    (net (code "82") (name "Net-(U5-BST)") (class "Default")
      (node (ref "C61") (pin "1") (pinfunction "1_1") (pintype "passive"))
      (node (ref "U5") (pin "1") (pinfunction "BST_1") (pintype "bidirectional"))
    )
    (net (code "83") (name "Net-(U5-FB)") (class "Default")
      (node (ref "C62") (pin "1") (pinfunction "1_1") (pintype "passive"))
      (node (ref "R47") (pin "2") (pinfunction "2_2") (pintype "passive"))
      (node (ref "R49") (pin "1") (pinfunction "1_1") (pintype "passive"))
      (node (ref "U5") (pin "6") (pinfunction "FB_6") (pintype "bidirectional"))
    )
    (net (code "84") (name "Net-(U5-INTVCC)") (class "Default")
      (node (ref "C60") (pin "1") (pinfunction "1_1") (pintype "passive"))
      (node (ref "U5") (pin "3") (pinfunction "INTVCC_3") (pintype "bidirectional"))
    )
    (net (code "85") (name "Net-(U5-PG)") (class "Default")
      (node (ref "R48") (pin "1") (pinfunction "1_1") (pintype "passive"))
      (node (ref "U5") (pin "8") (pinfunction "PG_8") (pintype "bidirectional"))
    )
    (net (code "86") (name "Net-(U5-RT)") (class "Default")
      (node (ref "R46") (pin "2") (pinfunction "2_2") (pintype "passive"))
      (node (ref "U5") (pin "4") (pinfunction "RT_4") (pintype "bidirectional"))
    )
    (net (code "87") (name "Net-(U5-SW)") (class "Default")
      (node (ref "C61") (pin "2") (pinfunction "2_2") (pintype "passive"))
      (node (ref "L6") (pin "1") (pinfunction "1_1") (pintype "bidirectional"))
      (node (ref "U5") (pin "2") (pinfunction "SW_2") (pintype "bidirectional"))
    )
    (net (code "88") (name "Net-(U5-TRSS)") (class "Default")
      (node (ref "C59") (pin "1") (pinfunction "1_1") (pintype "passive"))
      (node (ref "U5") (pin "7") (pinfunction "TRSS_7") (pintype "bidirectional"))
    )
    (net (code "89") (name "Net-(U6-BST)") (class "Default")
      (node (ref "C68") (pin "1") (pinfunction "1_1") (pintype "passive"))
      (node (ref "U6") (pin "1") (pinfunction "BST_1") (pintype "bidirectional"))
    )
    (net (code "90") (name "Net-(U6-FB)") (class "Default")
      (node (ref "C69") (pin "1") (pinfunction "1_1") (pintype "passive"))
      (node (ref "R51") (pin "2") (pinfunction "2_2") (pintype "passive"))
      (node (ref "R53") (pin "1") (pinfunction "1_1") (pintype "passive"))
      (node (ref "U6") (pin "6") (pinfunction "FB_6") (pintype "bidirectional"))
    )
    (net (code "91") (name "Net-(U6-INTVCC)") (class "Default")
      (node (ref "C67") (pin "1") (pinfunction "1_1") (pintype "passive"))
      (node (ref "U6") (pin "3") (pinfunction "INTVCC_3") (pintype "bidirectional"))
    )
    (net (code "92") (name "Net-(U6-PG)") (class "Default")
      (node (ref "R52") (pin "1") (pinfunction "1_1") (pintype "passive"))
      (node (ref "U6") (pin "8") (pinfunction "PG_8") (pintype "bidirectional"))
    )
    (net (code "93") (name "Net-(U6-RT)") (class "Default")
      (node (ref "R50") (pin "2") (pinfunction "2_2") (pintype "passive"))
      (node (ref "U6") (pin "4") (pinfunction "RT_4") (pintype "bidirectional"))
    )
    (net (code "94") (name "Net-(U6-SW)") (class "Default")
      (node (ref "C68") (pin "2") (pinfunction "2_2") (pintype "passive"))
      (node (ref "L7") (pin "1") (pinfunction "1_1") (pintype "bidirectional"))
      (node (ref "U6") (pin "2") (pinfunction "SW_2") (pintype "bidirectional"))
    )
    (net (code "95") (name "Net-(U6-TRSS)") (class "Default")
      (node (ref "C66") (pin "1") (pinfunction "1_1") (pintype "passive"))
      (node (ref "U6") (pin "7") (pinfunction "TRSS_7") (pintype "bidirectional"))
    )
    (net (code "96") (name "Net-(U7-BST)") (class "Default")
      (node (ref "C75") (pin "1") (pinfunction "1_1") (pintype "passive"))
      (node (ref "U7") (pin "1") (pinfunction "BST_1") (pintype "bidirectional"))
    )
    (net (code "97") (name "Net-(U7-FB)") (class "Default")
      (node (ref "C76") (pin "1") (pinfunction "1_1") (pintype "passive"))
      (node (ref "R55") (pin "2") (pinfunction "2_2") (pintype "passive"))
      (node (ref "R57") (pin "1") (pinfunction "1_1") (pintype "passive"))
      (node (ref "U7") (pin "6") (pinfunction "FB_6") (pintype "bidirectional"))
    )
    (net (code "98") (name "Net-(U7-INTVCC)") (class "Default")
      (node (ref "C74") (pin "1") (pinfunction "1_1") (pintype "passive"))
      (node (ref "U7") (pin "3") (pinfunction "INTVCC_3") (pintype "bidirectional"))
    )
    (net (code "99") (name "Net-(U7-PG)") (class "Default")
      (node (ref "R56") (pin "1") (pinfunction "1_1") (pintype "passive"))
      (node (ref "U7") (pin "8") (pinfunction "PG_8") (pintype "bidirectional"))
    )
    (net (code "100") (name "Net-(U7-RT)") (class "Default")
      (node (ref "R54") (pin "2") (pinfunction "2_2") (pintype "passive"))
      (node (ref "U7") (pin "4") (pinfunction "RT_4") (pintype "bidirectional"))
    )
    (net (code "101") (name "Net-(U7-SW)") (class "Default")
      (node (ref "C75") (pin "2") (pinfunction "2_2") (pintype "passive"))
      (node (ref "L8") (pin "1") (pinfunction "1_1") (pintype "bidirectional"))
      (node (ref "U7") (pin "2") (pinfunction "SW_2") (pintype "bidirectional"))
    )
    (net (code "102") (name "Net-(U7-TRSS)") (class "Default")
      (node (ref "C73") (pin "1") (pinfunction "1_1") (pintype "passive"))
      (node (ref "U7") (pin "7") (pinfunction "TRSS_7") (pintype "bidirectional"))
    )
    (net (code "103") (name "Net-(U8-BST)") (class "Default")
      (node (ref "C82") (pin "1") (pinfunction "1_1") (pintype "passive"))
      (node (ref "U8") (pin "1") (pinfunction "BST_1") (pintype "bidirectional"))
    )
    (net (code "104") (name "Net-(U8-FB)") (class "Default")
      (node (ref "C83") (pin "1") (pinfunction "1_1") (pintype "passive"))
      (node (ref "R59") (pin "2") (pinfunction "2_2") (pintype "passive"))
      (node (ref "R61") (pin "1") (pinfunction "1_1") (pintype "passive"))
      (node (ref "U8") (pin "6") (pinfunction "FB_6") (pintype "bidirectional"))
    )
    (net (code "105") (name "Net-(U8-INTVCC)") (class "Default")
      (node (ref "C81") (pin "1") (pinfunction "1_1") (pintype "passive"))
      (node (ref "U8") (pin "3") (pinfunction "INTVCC_3") (pintype "bidirectional"))
    )
    (net (code "106") (name "Net-(U8-PG)") (class "Default")
      (node (ref "R60") (pin "1") (pinfunction "1_1") (pintype "passive"))
      (node (ref "U8") (pin "8") (pinfunction "PG_8") (pintype "bidirectional"))
    )
    (net (code "107") (name "Net-(U8-RT)") (class "Default")
      (node (ref "R58") (pin "2") (pinfunction "2_2") (pintype "passive"))
      (node (ref "U8") (pin "4") (pinfunction "RT_4") (pintype "bidirectional"))
    )
    (net (code "108") (name "Net-(U8-SW)") (class "Default")
      (node (ref "C82") (pin "2") (pinfunction "2_2") (pintype "passive"))
      (node (ref "L9") (pin "1") (pinfunction "1_1") (pintype "bidirectional"))
      (node (ref "U8") (pin "2") (pinfunction "SW_2") (pintype "bidirectional"))
    )
    (net (code "109") (name "Net-(U8-TRSS)") (class "Default")
      (node (ref "C80") (pin "1") (pinfunction "1_1") (pintype "passive"))
      (node (ref "U8") (pin "7") (pinfunction "TRSS_7") (pintype "bidirectional"))
    )
    (net (code "110") (name "Net-(U19-ILIM)") (class "Default")
      (node (ref "R66") (pin "2") (pinfunction "2_2") (pintype "passive"))
      (node (ref "U19") (pin "4") (pinfunction "ILIM_4") (pintype "bidirectional"))
    )
    (net (code "111") (name "PCM_IN") (class "Default")
      (node (ref "C39") (pin "1") (pinfunction "1_1") (pintype "passive"))
      (node (ref "C40") (pin "1") (pinfunction "1_1") (pintype "passive"))
      (node (ref "C41") (pin "1") (pinfunction "1_1") (pintype "passive"))
      (node (ref "FB1") (pin "1") (pinfunction "1_1") (pintype "bidirectional"))
    )
    (net (code "112") (name "PCM_IN_FILTERED") (class "Default")
      (node (ref "C35") (pin "1") (pinfunction "1_1") (pintype "passive"))
      (node (ref "C42") (pin "1") (pinfunction "1_1") (pintype "passive"))
      (node (ref "C43") (pin "1") (pinfunction "1_1") (pintype "passive"))
      (node (ref "C44") (pin "1") (pinfunction "1_1") (pintype "passive"))
      (node (ref "C57") (pin "1") (pinfunction "1_1") (pintype "passive"))
      (node (ref "C58") (pin "1") (pinfunction "1_1") (pintype "passive"))
      (node (ref "C65") (pin "1") (pinfunction "1_1") (pintype "passive"))
      (node (ref "C72") (pin "1") (pinfunction "1_1") (pintype "passive"))
      (node (ref "C79") (pin "1") (pinfunction "1_1") (pintype "passive"))
      (node (ref "C86") (pin "1") (pinfunction "1_1") (pintype "passive"))
      (node (ref "FB1") (pin "2") (pinfunction "2_2") (pintype "bidirectional"))
      (node (ref "U2") (pin "1") (pinfunction "IN_1") (pintype "bidirectional"))
      (node (ref "U2") (pin "3") (pinfunction "EN_3") (pintype "bidirectional"))
      (node (ref "U3") (pin "10") (pinfunction "EN_10") (pintype "bidirectional"))
      (node (ref "U3") (pin "9") (pinfunction "VIN_9") (pintype "bidirectional"))
      (node (ref "U4") (pin "10") (pinfunction "EN_10") (pintype "bidirectional"))
      (node (ref "U4") (pin "9") (pinfunction "VIN_9") (pintype "bidirectional"))
      (node (ref "U5") (pin "10") (pinfunction "EN_10") (pintype "bidirectional"))
      (node (ref "U5") (pin "9") (pinfunction "VIN_9") (pintype "bidirectional"))
      (node (ref "U6") (pin "10") (pinfunction "EN_10") (pintype "bidirectional"))
      (node (ref "U6") (pin "9") (pinfunction "VIN_9") (pintype "bidirectional"))
      (node (ref "U7") (pin "10") (pinfunction "EN_10") (pintype "bidirectional"))
      (node (ref "U7") (pin "9") (pinfunction "VIN_9") (pintype "bidirectional"))
      (node (ref "U8") (pin "10") (pinfunction "EN_10") (pintype "bidirectional"))
      (node (ref "U8") (pin "9") (pinfunction "VIN_9") (pintype "bidirectional"))
    )
    (net (code "113") (name "SW1") (class "Default")
      (node (ref "C87") (pin "1") (pinfunction "1_1") (pintype "passive"))
      (node (ref "U9") (pin "1") (pinfunction "VOUT_1") (pintype "bidirectional"))
      (node (ref "U9") (pin "8") (pinfunction "VOUT_8") (pintype "bidirectional"))
    )
    (net (code "114") (name "SW1_EN") (class "Default")
      (node (ref "U9") (pin "4") (pinfunction "EN_4") (pintype "bidirectional"))
    )
    (net (code "115") (name "SW2") (class "Default")
      (node (ref "C88") (pin "1") (pinfunction "1_1") (pintype "passive"))
      (node (ref "U10") (pin "1") (pinfunction "VOUT_1") (pintype "bidirectional"))
      (node (ref "U10") (pin "8") (pinfunction "VOUT_8") (pintype "bidirectional"))
    )
    (net (code "116") (name "SW2_EN") (class "Default")
      (node (ref "U10") (pin "4") (pinfunction "EN_4") (pintype "bidirectional"))
    )
    (net (code "117") (name "SW3") (class "Default")
      (node (ref "C89") (pin "1") (pinfunction "1_1") (pintype "passive"))
      (node (ref "U11") (pin "1") (pinfunction "VOUT_1") (pintype "bidirectional"))
      (node (ref "U11") (pin "8") (pinfunction "VOUT_8") (pintype "bidirectional"))
    )
    (net (code "118") (name "SW3_EN") (class "Default")
      (node (ref "U11") (pin "4") (pinfunction "EN_4") (pintype "bidirectional"))
    )
    (net (code "119") (name "SW4") (class "Default")
      (node (ref "C90") (pin "1") (pinfunction "1_1") (pintype "passive"))
      (node (ref "U12") (pin "1") (pinfunction "VOUT_1") (pintype "bidirectional"))
      (node (ref "U12") (pin "8") (pinfunction "VOUT_8") (pintype "bidirectional"))
    )
    (net (code "120") (name "SW4_EN") (class "Default")
      (node (ref "U12") (pin "4") (pinfunction "EN_4") (pintype "bidirectional"))
    )
    (net (code "121") (name "SW5") (class "Default")
      (node (ref "C91") (pin "1") (pinfunction "1_1") (pintype "passive"))
      (node (ref "U13") (pin "1") (pinfunction "VOUT_1") (pintype "bidirectional"))
      (node (ref "U13") (pin "8") (pinfunction "VOUT_8") (pintype "bidirectional"))
    )
    (net (code "122") (name "SW5_EN") (class "Default")
      (node (ref "U13") (pin "4") (pinfunction "EN_4") (pintype "bidirectional"))
    )
    (net (code "123") (name "SW6") (class "Default")
      (node (ref "C92") (pin "1") (pinfunction "1_1") (pintype "passive"))
      (node (ref "U14") (pin "1") (pinfunction "VOUT_1") (pintype "bidirectional"))
      (node (ref "U14") (pin "8") (pinfunction "VOUT_8") (pintype "bidirectional"))
    )
    (net (code "124") (name "SW6_EN") (class "Default")
      (node (ref "U14") (pin "4") (pinfunction "EN_4") (pintype "bidirectional"))
    )
    (net (code "125") (name "SW7") (class "Default")
      (node (ref "C93") (pin "1") (pinfunction "1_1") (pintype "passive"))
      (node (ref "U15") (pin "1") (pinfunction "VOUT_1") (pintype "bidirectional"))
      (node (ref "U15") (pin "8") (pinfunction "VOUT_8") (pintype "bidirectional"))
    )
    (net (code "126") (name "SW7_EN") (class "Default")
      (node (ref "U15") (pin "4") (pinfunction "EN_4") (pintype "bidirectional"))
    )
    (net (code "127") (name "SW8") (class "Default")
      (node (ref "C94") (pin "1") (pinfunction "1_1") (pintype "passive"))
      (node (ref "U16") (pin "1") (pinfunction "VOUT_1") (pintype "bidirectional"))
      (node (ref "U16") (pin "8") (pinfunction "VOUT_8") (pintype "bidirectional"))
    )
    (net (code "128") (name "SW8_EN") (class "Default")
      (node (ref "U16") (pin "4") (pinfunction "EN_4") (pintype "bidirectional"))
    )
    (net (code "129") (name "SW9") (class "Default")
      (node (ref "C95") (pin "1") (pinfunction "1_1") (pintype "passive"))
      (node (ref "U17") (pin "1") (pinfunction "VOUT_1") (pintype "bidirectional"))
      (node (ref "U17") (pin "8") (pinfunction "VOUT_8") (pintype "bidirectional"))
    )
    (net (code "130") (name "SW9_EN") (class "Default")
      (node (ref "U17") (pin "4") (pinfunction "EN_4") (pintype "bidirectional"))
    )
    (net (code "131") (name "SW10") (class "Default")
      (node (ref "C96") (pin "1") (pinfunction "1_1") (pintype "passive"))
      (node (ref "U18") (pin "1") (pinfunction "VOUT_1") (pintype "bidirectional"))
      (node (ref "U18") (pin "8") (pinfunction "VOUT_8") (pintype "bidirectional"))
    )
    (net (code "132") (name "SW10_EN") (class "Default")
      (node (ref "U18") (pin "4") (pinfunction "EN_4") (pintype "bidirectional"))
    )
    (net (code "133") (name "U1_ESICI") (class "Default")
      (node (ref "U1") (pin "62") (pinfunction "ESICI_62") (pintype "input"))
    )
    (net (code "134") (name "U1_ESICOM") (class "Default")
      (node (ref "U1") (pin "63") (pinfunction "ESICOM_63") (pintype "passive"))
    )
    (net (code "135") (name "U1_ESIDVCC") (class "Default")
      (node (ref "U1") (pin "60") (pinfunction "ESIDVCC_60") (pintype "power_in"))
    )
    (net (code "136") (name "U1_ESIDVSS") (class "Default")
      (node (ref "U1") (pin "61") (pinfunction "ESIDVSS_61") (pintype "power_in"))
    )
    (net (code "137") (name "U1_I2C_SCL") (class "Default")
      (node (ref "R37") (pin "1") (pinfunction "1_1") (pintype "passive"))
      (node (ref "U1") (pin "77") (pinfunction "P4.1_UCB1SOMI_UCB1SCL_ACLK_S4_77") (pintype "bidirectional"))
    )
    (net (code "138") (name "U1_I2C_SDA") (class "Default")
      (node (ref "R36") (pin "1") (pinfunction "1_1") (pintype "passive"))
      (node (ref "U1") (pin "76") (pinfunction "P4.0_UCB1SIMO_UCB1SDA_MCLK_S5_76") (pintype "bidirectional"))
    )
    (net (code "139") (name "U1_LFXIN") (class "Default")
      (node (ref "C33") (pin "1") (pinfunction "1_1") (pintype "passive"))
      (node (ref "U1") (pin "69") (pinfunction "PJ.4_LFXIN_69") (pintype "bidirectional"))
      (node (ref "X1") (pin "1") (pinfunction "P$1_1") (pintype "bidirectional"))
    )
    (net (code "140") (name "U1_LFXOUT") (class "Default")
      (node (ref "C34") (pin "2") (pinfunction "2_2") (pintype "passive"))
      (node (ref "U1") (pin "70") (pinfunction "PJ.5_LFXOUT_70") (pintype "bidirectional"))
      (node (ref "X1") (pin "2") (pinfunction "P$2_2") (pintype "bidirectional"))
    )
    (net (code "141") (name "U1_PROG_RESET") (class "Default")
      (node (ref "U1") (pin "24") (pinfunction "RST_NMI_SBWTDIO_N_24") (pintype "bidirectional"))
    )
    (net (code "142") (name "U1_PROG_RXD") (class "Default")
      (node (ref "U1") (pin "35") (pinfunction "P3.5_UCA1SOMI_UCA1RXD_TB0.1_S20_35") (pintype "bidirectional"))
    )
    (net (code "143") (name "U1_PROG_TEST") (class "Default")
      (node (ref "U1") (pin "23") (pinfunction "TEST_SBWTCK_23") (pintype "input"))
    )
    (net (code "144") (name "U1_PROG_TXD") (class "Default")
      (node (ref "U1") (pin "34") (pinfunction "P3.4_UCA1SIMO_UCA1TXD_TB0.0_S21_34") (pintype "bidirectional"))
    )
    (net (code "145") (name "unconnected-(BCR1-~{ACOK}-Pad25)") (class "Default")
      (node (ref "BCR1") (pin "25") (pinfunction "~{ACOK}_25") (pintype "passive"))
    )
    (net (code "146") (name "unconnected-(BCR1-~{CHG}-Pad26)") (class "Default")
      (node (ref "BCR1") (pin "26") (pinfunction "~{CHG}_26") (pintype "passive"))
    )
    (net (code "147") (name "unconnected-(BCR1-~{PB}-Pad7)") (class "Default")
      (node (ref "BCR1") (pin "7") (pinfunction "~{PB}_7") (pintype "passive"))
    )
    (net (code "148") (name "unconnected-(BCR2-~{ACOK}-Pad25)") (class "Default")
      (node (ref "BCR2") (pin "25") (pinfunction "~{ACOK}_25") (pintype "passive"))
    )
    (net (code "149") (name "unconnected-(BCR2-~{CHG}-Pad26)") (class "Default")
      (node (ref "BCR2") (pin "26") (pinfunction "~{CHG}_26") (pintype "passive"))
    )
    (net (code "150") (name "unconnected-(BCR2-~{PB}-Pad7)") (class "Default")
      (node (ref "BCR2") (pin "7") (pinfunction "~{PB}_7") (pintype "passive"))
    )
    (net (code "151") (name "unconnected-(BCR3-~{ACOK}-Pad25)") (class "Default")
      (node (ref "BCR3") (pin "25") (pinfunction "~{ACOK}_25") (pintype "passive"))
    )
    (net (code "152") (name "unconnected-(BCR3-~{CHG}-Pad26)") (class "Default")
      (node (ref "BCR3") (pin "26") (pinfunction "~{CHG}_26") (pintype "passive"))
    )
    (net (code "153") (name "unconnected-(BCR3-~{PB}-Pad7)") (class "Default")
      (node (ref "BCR3") (pin "7") (pinfunction "~{PB}_7") (pintype "passive"))
    )
    (net (code "154") (name "unconnected-(H1-Pad1.1)") (class "Default")
      (node (ref "H1") (pin "1.1") (pinfunction "1.1_1.1") (pintype "bidirectional"))
    )
    (net (code "155") (name "unconnected-(H1-Pad1.2)") (class "Default")
      (node (ref "H1") (pin "1.2") (pinfunction "1.2_1.2") (pintype "bidirectional"))
    )
    (net (code "156") (name "unconnected-(H1-Pad1.3)") (class "Default")
      (node (ref "H1") (pin "1.3") (pinfunction "1.3_1.3") (pintype "bidirectional"))
    )
    (net (code "157") (name "unconnected-(H1-Pad1.4)") (class "Default")
      (node (ref "H1") (pin "1.4") (pinfunction "1.4_1.4") (pintype "bidirectional"))
    )
    (net (code "158") (name "unconnected-(H1-Pad1.5)") (class "Default")
      (node (ref "H1") (pin "1.5") (pinfunction "1.5_1.5") (pintype "bidirectional"))
    )
    (net (code "159") (name "unconnected-(H1-Pad1.6)") (class "Default")
      (node (ref "H1") (pin "1.6") (pinfunction "1.6_1.6") (pintype "bidirectional"))
    )
    (net (code "160") (name "unconnected-(H1-Pad1.7)") (class "Default")
      (node (ref "H1") (pin "1.7") (pinfunction "1.7_1.7") (pintype "bidirectional"))
    )
    (net (code "161") (name "unconnected-(H1-Pad1.8)") (class "Default")
      (node (ref "H1") (pin "1.8") (pinfunction "1.8_1.8") (pintype "bidirectional"))
    )
    (net (code "162") (name "unconnected-(H1-Pad1.9)") (class "Default")
      (node (ref "H1") (pin "1.9") (pinfunction "1.9_1.9") (pintype "bidirectional"))
    )
    (net (code "163") (name "unconnected-(H1-Pad1.10)") (class "Default")
      (node (ref "H1") (pin "1.10") (pinfunction "1.10_1.10") (pintype "bidirectional"))
    )
    (net (code "164") (name "unconnected-(H1-Pad1.11)") (class "Default")
      (node (ref "H1") (pin "1.11") (pinfunction "1.11_1.11") (pintype "bidirectional"))
    )
    (net (code "165") (name "unconnected-(H1-Pad1.12)") (class "Default")
      (node (ref "H1") (pin "1.12") (pinfunction "1.12_1.12") (pintype "bidirectional"))
    )
    (net (code "166") (name "unconnected-(H1-Pad1.13)") (class "Default")
      (node (ref "H1") (pin "1.13") (pinfunction "1.13_1.13") (pintype "bidirectional"))
    )
    (net (code "167") (name "unconnected-(H1-Pad1.14)") (class "Default")
      (node (ref "H1") (pin "1.14") (pinfunction "1.14_1.14") (pintype "bidirectional"))
    )
    (net (code "168") (name "unconnected-(H1-Pad1.15)") (class "Default")
      (node (ref "H1") (pin "1.15") (pinfunction "1.15_1.15") (pintype "bidirectional"))
    )
    (net (code "169") (name "unconnected-(H1-Pad1.16)") (class "Default")
      (node (ref "H1") (pin "1.16") (pinfunction "1.16_1.16") (pintype "bidirectional"))
    )
    (net (code "170") (name "unconnected-(H1-Pad1.17)") (class "Default")
      (node (ref "H1") (pin "1.17") (pinfunction "1.17_1.17") (pintype "bidirectional"))
    )
    (net (code "171") (name "unconnected-(H1-Pad1.18)") (class "Default")
      (node (ref "H1") (pin "1.18") (pinfunction "1.18_1.18") (pintype "bidirectional"))
    )
    (net (code "172") (name "unconnected-(H1-Pad1.19)") (class "Default")
      (node (ref "H1") (pin "1.19") (pinfunction "1.19_1.19") (pintype "bidirectional"))
    )
    (net (code "173") (name "unconnected-(H1-Pad1.20)") (class "Default")
      (node (ref "H1") (pin "1.20") (pinfunction "1.20_1.20") (pintype "bidirectional"))
    )
    (net (code "174") (name "unconnected-(H1-Pad1.21)") (class "Default")
      (node (ref "H1") (pin "1.21") (pinfunction "1.21_1.21") (pintype "bidirectional"))
    )
    (net (code "175") (name "unconnected-(H1-Pad1.22)") (class "Default")
      (node (ref "H1") (pin "1.22") (pinfunction "1.22_1.22") (pintype "bidirectional"))
    )
    (net (code "176") (name "unconnected-(H1-Pad1.23)") (class "Default")
      (node (ref "H1") (pin "1.23") (pinfunction "1.23_1.23") (pintype "bidirectional"))
    )
    (net (code "177") (name "unconnected-(H1-Pad1.24)") (class "Default")
      (node (ref "H1") (pin "1.24") (pinfunction "1.24_1.24") (pintype "bidirectional"))
    )
    (net (code "178") (name "unconnected-(H1-Pad1.25)") (class "Default")
      (node (ref "H1") (pin "1.25") (pinfunction "1.25_1.25") (pintype "bidirectional"))
    )
    (net (code "179") (name "unconnected-(H1-Pad1.26)") (class "Default")
      (node (ref "H1") (pin "1.26") (pinfunction "1.26_1.26") (pintype "bidirectional"))
    )
    (net (code "180") (name "unconnected-(H1-Pad1.27)") (class "Default")
      (node (ref "H1") (pin "1.27") (pinfunction "1.27_1.27") (pintype "bidirectional"))
    )
    (net (code "181") (name "unconnected-(H1-Pad1.28)") (class "Default")
      (node (ref "H1") (pin "1.28") (pinfunction "1.28_1.28") (pintype "bidirectional"))
    )
    (net (code "182") (name "unconnected-(H1-Pad1.29)") (class "Default")
      (node (ref "H1") (pin "1.29") (pinfunction "1.29_1.29") (pintype "bidirectional"))
    )
    (net (code "183") (name "unconnected-(H1-Pad1.30)") (class "Default")
      (node (ref "H1") (pin "1.30") (pinfunction "1.30_1.30") (pintype "bidirectional"))
    )
    (net (code "184") (name "unconnected-(H1-Pad1.31)") (class "Default")
      (node (ref "H1") (pin "1.31") (pinfunction "1.31_1.31") (pintype "bidirectional"))
    )
    (net (code "185") (name "unconnected-(H1-Pad1.32)") (class "Default")
      (node (ref "H1") (pin "1.32") (pinfunction "1.32_1.32") (pintype "bidirectional"))
    )
    (net (code "186") (name "unconnected-(H1-Pad1.33)") (class "Default")
      (node (ref "H1") (pin "1.33") (pinfunction "1.33_1.33") (pintype "bidirectional"))
    )
    (net (code "187") (name "unconnected-(H1-Pad1.34)") (class "Default")
      (node (ref "H1") (pin "1.34") (pinfunction "1.34_1.34") (pintype "bidirectional"))
    )
    (net (code "188") (name "unconnected-(H1-Pad1.35)") (class "Default")
      (node (ref "H1") (pin "1.35") (pinfunction "1.35_1.35") (pintype "bidirectional"))
    )
    (net (code "189") (name "unconnected-(H1-Pad1.36)") (class "Default")
      (node (ref "H1") (pin "1.36") (pinfunction "1.36_1.36") (pintype "bidirectional"))
    )
    (net (code "190") (name "unconnected-(H1-Pad1.37)") (class "Default")
      (node (ref "H1") (pin "1.37") (pinfunction "1.37_1.37") (pintype "bidirectional"))
    )
    (net (code "191") (name "unconnected-(H1-Pad1.38)") (class "Default")
      (node (ref "H1") (pin "1.38") (pinfunction "1.38_1.38") (pintype "bidirectional"))
    )
    (net (code "192") (name "unconnected-(H1-Pad1.39)") (class "Default")
      (node (ref "H1") (pin "1.39") (pinfunction "1.39_1.39") (pintype "bidirectional"))
    )
    (net (code "193") (name "unconnected-(H1-Pad1.40)") (class "Default")
      (node (ref "H1") (pin "1.40") (pinfunction "1.40_1.40") (pintype "bidirectional"))
    )
    (net (code "194") (name "unconnected-(H1-Pad1.41)") (class "Default")
      (node (ref "H1") (pin "1.41") (pinfunction "1.41_1.41") (pintype "bidirectional"))
    )
    (net (code "195") (name "unconnected-(H1-Pad1.42)") (class "Default")
      (node (ref "H1") (pin "1.42") (pinfunction "1.42_1.42") (pintype "bidirectional"))
    )
    (net (code "196") (name "unconnected-(H1-Pad1.43)") (class "Default")
      (node (ref "H1") (pin "1.43") (pinfunction "1.43_1.43") (pintype "bidirectional"))
    )
    (net (code "197") (name "unconnected-(H1-Pad1.44)") (class "Default")
      (node (ref "H1") (pin "1.44") (pinfunction "1.44_1.44") (pintype "bidirectional"))
    )
    (net (code "198") (name "unconnected-(H1-Pad1.45)") (class "Default")
      (node (ref "H1") (pin "1.45") (pinfunction "1.45_1.45") (pintype "bidirectional"))
    )
    (net (code "199") (name "unconnected-(H1-Pad1.46)") (class "Default")
      (node (ref "H1") (pin "1.46") (pinfunction "1.46_1.46") (pintype "bidirectional"))
    )
    (net (code "200") (name "unconnected-(H1-Pad1.47)") (class "Default")
      (node (ref "H1") (pin "1.47") (pinfunction "1.47_1.47") (pintype "bidirectional"))
    )
    (net (code "201") (name "unconnected-(H1-Pad1.48)") (class "Default")
      (node (ref "H1") (pin "1.48") (pinfunction "1.48_1.48") (pintype "bidirectional"))
    )
    (net (code "202") (name "unconnected-(H1-Pad1.49)") (class "Default")
      (node (ref "H1") (pin "1.49") (pinfunction "1.49_1.49") (pintype "bidirectional"))
    )
    (net (code "203") (name "unconnected-(H1-Pad1.50)") (class "Default")
      (node (ref "H1") (pin "1.50") (pinfunction "1.50_1.50") (pintype "bidirectional"))
    )
    (net (code "204") (name "unconnected-(H1-Pad1.51)") (class "Default")
      (node (ref "H1") (pin "1.51") (pinfunction "1.51_1.51") (pintype "bidirectional"))
    )
    (net (code "205") (name "unconnected-(H1-Pad1.52)") (class "Default")
      (node (ref "H1") (pin "1.52") (pinfunction "1.52_1.52") (pintype "bidirectional"))
    )
    (net (code "206") (name "unconnected-(H1-Pad2.1)") (class "Default")
      (node (ref "H1") (pin "2.1") (pinfunction "2.1_2.1") (pintype "bidirectional"))
    )
    (net (code "207") (name "unconnected-(H1-Pad2.2)") (class "Default")
      (node (ref "H1") (pin "2.2") (pinfunction "2.2_2.2") (pintype "bidirectional"))
    )
    (net (code "208") (name "unconnected-(H1-Pad2.3)") (class "Default")
      (node (ref "H1") (pin "2.3") (pinfunction "2.3_2.3") (pintype "bidirectional"))
    )
    (net (code "209") (name "unconnected-(H1-Pad2.4)") (class "Default")
      (node (ref "H1") (pin "2.4") (pinfunction "2.4_2.4") (pintype "bidirectional"))
    )
    (net (code "210") (name "unconnected-(H1-Pad2.5)") (class "Default")
      (node (ref "H1") (pin "2.5") (pinfunction "2.5_2.5") (pintype "bidirectional"))
    )
    (net (code "211") (name "unconnected-(H1-Pad2.6)") (class "Default")
      (node (ref "H1") (pin "2.6") (pinfunction "2.6_2.6") (pintype "bidirectional"))
    )
    (net (code "212") (name "unconnected-(H1-Pad2.7)") (class "Default")
      (node (ref "H1") (pin "2.7") (pinfunction "2.7_2.7") (pintype "bidirectional"))
    )
    (net (code "213") (name "unconnected-(H1-Pad2.8)") (class "Default")
      (node (ref "H1") (pin "2.8") (pinfunction "2.8_2.8") (pintype "bidirectional"))
    )
    (net (code "214") (name "unconnected-(H1-Pad2.9)") (class "Default")
      (node (ref "H1") (pin "2.9") (pinfunction "2.9_2.9") (pintype "bidirectional"))
    )
    (net (code "215") (name "unconnected-(H1-Pad2.10)") (class "Default")
      (node (ref "H1") (pin "2.10") (pinfunction "2.10_2.10") (pintype "bidirectional"))
    )
    (net (code "216") (name "unconnected-(H1-Pad2.11)") (class "Default")
      (node (ref "H1") (pin "2.11") (pinfunction "2.11_2.11") (pintype "bidirectional"))
    )
    (net (code "217") (name "unconnected-(H1-Pad2.12)") (class "Default")
      (node (ref "H1") (pin "2.12") (pinfunction "2.12_2.12") (pintype "bidirectional"))
    )
    (net (code "218") (name "unconnected-(H1-Pad2.13)") (class "Default")
      (node (ref "H1") (pin "2.13") (pinfunction "2.13_2.13") (pintype "bidirectional"))
    )
    (net (code "219") (name "unconnected-(H1-Pad2.14)") (class "Default")
      (node (ref "H1") (pin "2.14") (pinfunction "2.14_2.14") (pintype "bidirectional"))
    )
    (net (code "220") (name "unconnected-(H1-Pad2.15)") (class "Default")
      (node (ref "H1") (pin "2.15") (pinfunction "2.15_2.15") (pintype "bidirectional"))
    )
    (net (code "221") (name "unconnected-(H1-Pad2.16)") (class "Default")
      (node (ref "H1") (pin "2.16") (pinfunction "2.16_2.16") (pintype "bidirectional"))
    )
    (net (code "222") (name "unconnected-(H1-Pad2.17)") (class "Default")
      (node (ref "H1") (pin "2.17") (pinfunction "2.17_2.17") (pintype "bidirectional"))
    )
    (net (code "223") (name "unconnected-(H1-Pad2.18)") (class "Default")
      (node (ref "H1") (pin "2.18") (pinfunction "2.18_2.18") (pintype "bidirectional"))
    )
    (net (code "224") (name "unconnected-(H1-Pad2.19)") (class "Default")
      (node (ref "H1") (pin "2.19") (pinfunction "2.19_2.19") (pintype "bidirectional"))
    )
    (net (code "225") (name "unconnected-(H1-Pad2.20)") (class "Default")
      (node (ref "H1") (pin "2.20") (pinfunction "2.20_2.20") (pintype "bidirectional"))
    )
    (net (code "226") (name "unconnected-(H1-Pad2.21)") (class "Default")
      (node (ref "H1") (pin "2.21") (pinfunction "2.21_2.21") (pintype "bidirectional"))
    )
    (net (code "227") (name "unconnected-(H1-Pad2.22)") (class "Default")
      (node (ref "H1") (pin "2.22") (pinfunction "2.22_2.22") (pintype "bidirectional"))
    )
    (net (code "228") (name "unconnected-(H1-Pad2.23)") (class "Default")
      (node (ref "H1") (pin "2.23") (pinfunction "2.23_2.23") (pintype "bidirectional"))
    )
    (net (code "229") (name "unconnected-(H1-Pad2.24)") (class "Default")
      (node (ref "H1") (pin "2.24") (pinfunction "2.24_2.24") (pintype "bidirectional"))
    )
    (net (code "230") (name "unconnected-(H1-Pad2.25)") (class "Default")
      (node (ref "H1") (pin "2.25") (pinfunction "2.25_2.25") (pintype "bidirectional"))
    )
    (net (code "231") (name "unconnected-(H1-Pad2.26)") (class "Default")
      (node (ref "H1") (pin "2.26") (pinfunction "2.26_2.26") (pintype "bidirectional"))
    )
    (net (code "232") (name "unconnected-(H1-Pad2.27)") (class "Default")
      (node (ref "H1") (pin "2.27") (pinfunction "2.27_2.27") (pintype "bidirectional"))
    )
    (net (code "233") (name "unconnected-(H1-Pad2.28)") (class "Default")
      (node (ref "H1") (pin "2.28") (pinfunction "2.28_2.28") (pintype "bidirectional"))
    )
    (net (code "234") (name "unconnected-(H1-Pad2.29)") (class "Default")
      (node (ref "H1") (pin "2.29") (pinfunction "2.29_2.29") (pintype "bidirectional"))
    )
    (net (code "235") (name "unconnected-(H1-Pad2.30)") (class "Default")
      (node (ref "H1") (pin "2.30") (pinfunction "2.30_2.30") (pintype "bidirectional"))
    )
    (net (code "236") (name "unconnected-(H1-Pad2.31)") (class "Default")
      (node (ref "H1") (pin "2.31") (pinfunction "2.31_2.31") (pintype "bidirectional"))
    )
    (net (code "237") (name "unconnected-(H1-Pad2.32)") (class "Default")
      (node (ref "H1") (pin "2.32") (pinfunction "2.32_2.32") (pintype "bidirectional"))
    )
    (net (code "238") (name "unconnected-(H1-Pad2.33)") (class "Default")
      (node (ref "H1") (pin "2.33") (pinfunction "2.33_2.33") (pintype "bidirectional"))
    )
    (net (code "239") (name "unconnected-(H1-Pad2.34)") (class "Default")
      (node (ref "H1") (pin "2.34") (pinfunction "2.34_2.34") (pintype "bidirectional"))
    )
    (net (code "240") (name "unconnected-(H1-Pad2.35)") (class "Default")
      (node (ref "H1") (pin "2.35") (pinfunction "2.35_2.35") (pintype "bidirectional"))
    )
    (net (code "241") (name "unconnected-(H1-Pad2.36)") (class "Default")
      (node (ref "H1") (pin "2.36") (pinfunction "2.36_2.36") (pintype "bidirectional"))
    )
    (net (code "242") (name "unconnected-(H1-Pad2.37)") (class "Default")
      (node (ref "H1") (pin "2.37") (pinfunction "2.37_2.37") (pintype "bidirectional"))
    )
    (net (code "243") (name "unconnected-(H1-Pad2.38)") (class "Default")
      (node (ref "H1") (pin "2.38") (pinfunction "2.38_2.38") (pintype "bidirectional"))
    )
    (net (code "244") (name "unconnected-(H1-Pad2.39)") (class "Default")
      (node (ref "H1") (pin "2.39") (pinfunction "2.39_2.39") (pintype "bidirectional"))
    )
    (net (code "245") (name "unconnected-(H1-Pad2.40)") (class "Default")
      (node (ref "H1") (pin "2.40") (pinfunction "2.40_2.40") (pintype "bidirectional"))
    )
    (net (code "246") (name "unconnected-(H1-Pad2.41)") (class "Default")
      (node (ref "H1") (pin "2.41") (pinfunction "2.41_2.41") (pintype "bidirectional"))
    )
    (net (code "247") (name "unconnected-(H1-Pad2.42)") (class "Default")
      (node (ref "H1") (pin "2.42") (pinfunction "2.42_2.42") (pintype "bidirectional"))
    )
    (net (code "248") (name "unconnected-(H1-Pad2.43)") (class "Default")
      (node (ref "H1") (pin "2.43") (pinfunction "2.43_2.43") (pintype "bidirectional"))
    )
    (net (code "249") (name "unconnected-(H1-Pad2.44)") (class "Default")
      (node (ref "H1") (pin "2.44") (pinfunction "2.44_2.44") (pintype "bidirectional"))
    )
    (net (code "250") (name "unconnected-(H1-Pad2.45)") (class "Default")
      (node (ref "H1") (pin "2.45") (pinfunction "2.45_2.45") (pintype "bidirectional"))
    )
    (net (code "251") (name "unconnected-(H1-Pad2.46)") (class "Default")
      (node (ref "H1") (pin "2.46") (pinfunction "2.46_2.46") (pintype "bidirectional"))
    )
    (net (code "252") (name "unconnected-(H1-Pad2.47)") (class "Default")
      (node (ref "H1") (pin "2.47") (pinfunction "2.47_2.47") (pintype "bidirectional"))
    )
    (net (code "253") (name "unconnected-(H1-Pad2.48)") (class "Default")
      (node (ref "H1") (pin "2.48") (pinfunction "2.48_2.48") (pintype "bidirectional"))
    )
    (net (code "254") (name "unconnected-(H1-Pad2.49)") (class "Default")
      (node (ref "H1") (pin "2.49") (pinfunction "2.49_2.49") (pintype "bidirectional"))
    )
    (net (code "255") (name "unconnected-(H1-Pad2.50)") (class "Default")
      (node (ref "H1") (pin "2.50") (pinfunction "2.50_2.50") (pintype "bidirectional"))
    )
    (net (code "256") (name "unconnected-(H1-Pad2.51)") (class "Default")
      (node (ref "H1") (pin "2.51") (pinfunction "2.51_2.51") (pintype "bidirectional"))
    )
    (net (code "257") (name "unconnected-(H1-Pad2.52)") (class "Default")
      (node (ref "H1") (pin "2.52") (pinfunction "2.52_2.52") (pintype "bidirectional"))
    )
    (net (code "258") (name "unconnected-(H1-PadP1)") (class "Default")
      (node (ref "H1") (pin "P1") (pinfunction "P1_P1") (pintype "bidirectional"))
    )
    (net (code "259") (name "unconnected-(H1-PadP2)") (class "Default")
      (node (ref "H1") (pin "P2") (pinfunction "P2_P2") (pintype "bidirectional"))
    )
    (net (code "260") (name "unconnected-(H1-PadP3)") (class "Default")
      (node (ref "H1") (pin "P3") (pinfunction "P3_P3") (pintype "bidirectional"))
    )
    (net (code "261") (name "unconnected-(H1-PadP4)") (class "Default")
      (node (ref "H1") (pin "P4") (pinfunction "P4_P4") (pintype "bidirectional"))
    )
    (net (code "262") (name "unconnected-(J1-SBU1-PadA8)") (class "Default")
      (node (ref "J1") (pin "A8") (pinfunction "SBU1_A8") (pintype "bidirectional"))
    )
    (net (code "263") (name "unconnected-(J1-SBU2-PadB8)") (class "Default")
      (node (ref "J1") (pin "B8") (pinfunction "SBU2_B8") (pintype "bidirectional"))
    )
    (net (code "264") (name "unconnected-(J1-SSRXN1-PadB10)") (class "Default")
      (node (ref "J1") (pin "B10") (pinfunction "SSRXN1_B10") (pintype "bidirectional"))
    )
    (net (code "265") (name "unconnected-(J1-SSRXN2-PadA10)") (class "Default")
      (node (ref "J1") (pin "A10") (pinfunction "SSRXN2_A10") (pintype "bidirectional"))
    )
    (net (code "266") (name "unconnected-(J1-SSRXP1-PadB11)") (class "Default")
      (node (ref "J1") (pin "B11") (pinfunction "SSRXP1_B11") (pintype "bidirectional"))
    )
    (net (code "267") (name "unconnected-(J1-SSRXP2-PadA11)") (class "Default")
      (node (ref "J1") (pin "A11") (pinfunction "SSRXP2_A11") (pintype "bidirectional"))
    )
    (net (code "268") (name "unconnected-(J1-SSTXN1-PadA3)") (class "Default")
      (node (ref "J1") (pin "A3") (pinfunction "SSTXN1_A3") (pintype "bidirectional"))
    )
    (net (code "269") (name "unconnected-(J1-SSTXN2-PadB3)") (class "Default")
      (node (ref "J1") (pin "B3") (pinfunction "SSTXN2_B3") (pintype "bidirectional"))
    )
    (net (code "270") (name "unconnected-(J1-SSTXP1-PadA2)") (class "Default")
      (node (ref "J1") (pin "A2") (pinfunction "SSTXP1_A2") (pintype "bidirectional"))
    )
    (net (code "271") (name "unconnected-(J1-SSTXP2-PadB2)") (class "Default")
      (node (ref "J1") (pin "B2") (pinfunction "SSTXP2_B2") (pintype "bidirectional"))
    )
    (net (code "272") (name "unconnected-(J2-SBU1-PadA8)") (class "Default")
      (node (ref "J2") (pin "A8") (pinfunction "SBU1_A8") (pintype "bidirectional"))
    )
    (net (code "273") (name "unconnected-(J2-SBU2-PadB8)") (class "Default")
      (node (ref "J2") (pin "B8") (pinfunction "SBU2_B8") (pintype "bidirectional"))
    )
    (net (code "274") (name "unconnected-(J2-SSRXN1-PadB10)") (class "Default")
      (node (ref "J2") (pin "B10") (pinfunction "SSRXN1_B10") (pintype "bidirectional"))
    )
    (net (code "275") (name "unconnected-(J2-SSRXN2-PadA10)") (class "Default")
      (node (ref "J2") (pin "A10") (pinfunction "SSRXN2_A10") (pintype "bidirectional"))
    )
    (net (code "276") (name "unconnected-(J2-SSRXP1-PadB11)") (class "Default")
      (node (ref "J2") (pin "B11") (pinfunction "SSRXP1_B11") (pintype "bidirectional"))
    )
    (net (code "277") (name "unconnected-(J2-SSRXP2-PadA11)") (class "Default")
      (node (ref "J2") (pin "A11") (pinfunction "SSRXP2_A11") (pintype "bidirectional"))
    )
    (net (code "278") (name "unconnected-(J2-SSTXN1-PadA3)") (class "Default")
      (node (ref "J2") (pin "A3") (pinfunction "SSTXN1_A3") (pintype "bidirectional"))
    )
    (net (code "279") (name "unconnected-(J2-SSTXN2-PadB3)") (class "Default")
      (node (ref "J2") (pin "B3") (pinfunction "SSTXN2_B3") (pintype "bidirectional"))
    )
    (net (code "280") (name "unconnected-(J2-SSTXP1-PadA2)") (class "Default")
      (node (ref "J2") (pin "A2") (pinfunction "SSTXP1_A2") (pintype "bidirectional"))
    )
    (net (code "281") (name "unconnected-(J2-SSTXP2-PadB2)") (class "Default")
      (node (ref "J2") (pin "B2") (pinfunction "SSTXP2_B2") (pintype "bidirectional"))
    )
    (net (code "282") (name "unconnected-(U1-P1.0_TA0.1_DMAE0_RTCCLK_A0_C0_VREF-_VEREF--Pad51)") (class "Default")
      (node (ref "U1") (pin "51") (pinfunction "P1.0_TA0.1_DMAE0_RTCCLK_A0_C0_VREF-_VEREF-_51") (pintype "bidirectional"))
    )
    (net (code "283") (name "unconnected-(U1-P1.1_TA0.2_TA1CLK_COUT_A1_C1_VREF+_VEREF+-Pad50)") (class "Default")
      (node (ref "U1") (pin "50") (pinfunction "P1.1_TA0.2_TA1CLK_COUT_A1_C1_VREF+_VEREF+_50") (pintype "bidirectional"))
    )
    (net (code "284") (name "unconnected-(U1-P1.2_TA1.1_TA0CLK_COUT_A2_C2-Pad49)") (class "Default")
      (node (ref "U1") (pin "49") (pinfunction "P1.2_TA1.1_TA0CLK_COUT_A2_C2_49") (pintype "bidirectional"))
    )
    (net (code "285") (name "unconnected-(U1-P1.3_TA1.2_ESITEST4_A3_C3-Pad48)") (class "Default")
      (node (ref "U1") (pin "48") (pinfunction "P1.3_TA1.2_ESITEST4_A3_C3_48") (pintype "bidirectional"))
    )
    (net (code "286") (name "unconnected-(U1-P1.4_UCB0CLK_UCA0STE_TA1.0_S3-Pad2)") (class "Default")
      (node (ref "U1") (pin "2") (pinfunction "P1.4_UCB0CLK_UCA0STE_TA1.0_S3_2") (pintype "bidirectional"))
    )
    (net (code "287") (name "unconnected-(U1-P1.5_UCB0STE_UCA0CLK_TA0.0_S2-Pad3)") (class "Default")
      (node (ref "U1") (pin "3") (pinfunction "P1.5_UCB0STE_UCA0CLK_TA0.0_S2_3") (pintype "bidirectional"))
    )
    (net (code "288") (name "unconnected-(U1-P1.6_UCB0SIMO_UCB0SDA_TA0.1_S1-Pad4)") (class "Default")
      (node (ref "U1") (pin "4") (pinfunction "P1.6_UCB0SIMO_UCB0SDA_TA0.1_S1_4") (pintype "bidirectional"))
    )
    (net (code "289") (name "unconnected-(U1-P1.7_UCB0SOMI_UCB0SCL_TA0.2_S0-Pad5)") (class "Default")
      (node (ref "U1") (pin "5") (pinfunction "P1.7_UCB0SOMI_UCB0SCL_TA0.2_S0_5") (pintype "bidirectional"))
    )
    (net (code "290") (name "unconnected-(U1-P2.0_UCA0SIMO_UCA0TXD_TB0.6_TB0CLK_S14-Pad41)") (class "Default")
      (node (ref "U1") (pin "41") (pinfunction "P2.0_UCA0SIMO_UCA0TXD_TB0.6_TB0CLK_S14_41") (pintype "bidirectional"))
    )
    (net (code "291") (name "unconnected-(U1-P2.1_UCA0SOMI_UCA0RXD_TB0.5_DMAE0_S15-Pad40)") (class "Default")
      (node (ref "U1") (pin "40") (pinfunction "P2.1_UCA0SOMI_UCA0RXD_TB0.5_DMAE0_S15_40") (pintype "bidirectional"))
    )
    (net (code "292") (name "unconnected-(U1-P2.2_UCA0CLK_TB0.4_RTCCLK_S16-Pad39)") (class "Default")
      (node (ref "U1") (pin "39") (pinfunction "P2.2_UCA0CLK_TB0.4_RTCCLK_S16_39") (pintype "bidirectional"))
    )
    (net (code "293") (name "unconnected-(U1-P2.3_UCA0STE_TB0OUTH_S17-Pad38)") (class "Default")
      (node (ref "U1") (pin "38") (pinfunction "P2.3_UCA0STE_TB0OUTH_S17_38") (pintype "bidirectional"))
    )
    (net (code "294") (name "unconnected-(U1-P2.4_TB0.3_COM4_S33-Pad14)") (class "Default")
      (node (ref "U1") (pin "14") (pinfunction "P2.4_TB0.3_COM4_S33_14") (pintype "bidirectional"))
    )
    (net (code "295") (name "unconnected-(U1-P2.5_TB0.4_COM5_S32-Pad15)") (class "Default")
      (node (ref "U1") (pin "15") (pinfunction "P2.5_TB0.4_COM5_S32_15") (pintype "bidirectional"))
    )
    (net (code "296") (name "unconnected-(U1-P2.6_TB0.5_ESIC1OUT_COM6_S31-Pad16)") (class "Default")
      (node (ref "U1") (pin "16") (pinfunction "P2.6_TB0.5_ESIC1OUT_COM6_S31_16") (pintype "bidirectional"))
    )
    (net (code "297") (name "unconnected-(U1-P2.7_TB0.6_ESIC2OUT_COM7_S30-Pad17)") (class "Default")
      (node (ref "U1") (pin "17") (pinfunction "P2.7_TB0.6_ESIC2OUT_COM7_S30_17") (pintype "bidirectional"))
    )
    (net (code "298") (name "unconnected-(U1-P3.0_UCB1CLK_S29-Pad18)") (class "Default")
      (node (ref "U1") (pin "18") (pinfunction "P3.0_UCB1CLK_S29_18") (pintype "bidirectional"))
    )
    (net (code "299") (name "unconnected-(U1-P3.1_UCB1SIMO_UCB1SDA_S28-Pad19)") (class "Default")
      (node (ref "U1") (pin "19") (pinfunction "P3.1_UCB1SIMO_UCB1SDA_S28_19") (pintype "bidirectional"))
    )
    (net (code "300") (name "unconnected-(U1-P3.2_UCB1SOMI_UCB1SCL_S27-Pad20)") (class "Default")
      (node (ref "U1") (pin "20") (pinfunction "P3.2_UCB1SOMI_UCB1SCL_S27_20") (pintype "bidirectional"))
    )
    (net (code "301") (name "unconnected-(U1-P3.3_TA1.1_TB0CLK_S22-Pad33)") (class "Default")
      (node (ref "U1") (pin "33") (pinfunction "P3.3_TA1.1_TB0CLK_S22_33") (pintype "bidirectional"))
    )
    (net (code "302") (name "unconnected-(U1-P3.6_UCA1CLK_TB0.2_S19-Pad36)") (class "Default")
      (node (ref "U1") (pin "36") (pinfunction "P3.6_UCA1CLK_TB0.2_S19_36") (pintype "bidirectional"))
    )
    (net (code "303") (name "unconnected-(U1-P3.7_UCA1STE_TB0.3_S18-Pad37)") (class "Default")
      (node (ref "U1") (pin "37") (pinfunction "P3.7_UCA1STE_TB0.3_S18_37") (pintype "bidirectional"))
    )
    (net (code "304") (name "unconnected-(U1-P4.2_UCA0SIMO_UCA0TXD_UCB1CLK-Pad80)") (class "Default")
      (node (ref "U1") (pin "80") (pinfunction "P4.2_UCA0SIMO_UCA0TXD_UCB1CLK_80") (pintype "bidirectional"))
    )
    (net (code "305") (name "unconnected-(U1-P4.3_UCA0SOMI_UCA0RXD_UCB1STE-Pad1)") (class "Default")
      (node (ref "U1") (pin "1") (pinfunction "P4.3_UCA0SOMI_UCA0RXD_UCB1STE_1") (pintype "bidirectional"))
    )
    (net (code "306") (name "unconnected-(U1-P4.4_UCB1STE_TA1CLK_S9-Pad72)") (class "Default")
      (node (ref "U1") (pin "72") (pinfunction "P4.4_UCB1STE_TA1CLK_S9_72") (pintype "bidirectional"))
    )
    (net (code "307") (name "unconnected-(U1-P4.5_UCB1CLK_TA1.0_S8-Pad73)") (class "Default")
      (node (ref "U1") (pin "73") (pinfunction "P4.5_UCB1CLK_TA1.0_S8_73") (pintype "bidirectional"))
    )
    (net (code "308") (name "unconnected-(U1-P4.6_UCB1SIMO_UCB1SDA_TA1.1_S7-Pad74)") (class "Default")
      (node (ref "U1") (pin "74") (pinfunction "P4.6_UCB1SIMO_UCB1SDA_TA1.1_S7_74") (pintype "bidirectional"))
    )
    (net (code "309") (name "unconnected-(U1-P4.7_UCB1SOMI_UCB1SCL_TA1.2_S6-Pad75)") (class "Default")
      (node (ref "U1") (pin "75") (pinfunction "P4.7_UCB1SOMI_UCB1SCL_TA1.2_S6_75") (pintype "bidirectional"))
    )
    (net (code "310") (name "unconnected-(U1-P6.0_R23-Pad7)") (class "Default")
      (node (ref "U1") (pin "7") (pinfunction "P6.0_R23_7") (pintype "bidirectional"))
    )
    (net (code "311") (name "unconnected-(U1-P6.1_R13_LCDREF-Pad8)") (class "Default")
      (node (ref "U1") (pin "8") (pinfunction "P6.1_R13_LCDREF_8") (pintype "bidirectional"))
    )
    (net (code "312") (name "unconnected-(U1-P6.2_COUT_R03-Pad9)") (class "Default")
      (node (ref "U1") (pin "9") (pinfunction "P6.2_COUT_R03_9") (pintype "bidirectional"))
    )
    (net (code "313") (name "unconnected-(U1-P6.3_COM0-Pad10)") (class "Default")
      (node (ref "U1") (pin "10") (pinfunction "P6.3_COM0_10") (pintype "bidirectional"))
    )
    (net (code "314") (name "unconnected-(U1-P6.4_TB0.0_COM1_S36-Pad11)") (class "Default")
      (node (ref "U1") (pin "11") (pinfunction "P6.4_TB0.0_COM1_S36_11") (pintype "bidirectional"))
    )
    (net (code "315") (name "unconnected-(U1-P6.5_TB0.1_COM2_S35-Pad12)") (class "Default")
      (node (ref "U1") (pin "12") (pinfunction "P6.5_TB0.1_COM2_S35_12") (pintype "bidirectional"))
    )
    (net (code "316") (name "unconnected-(U1-P6.6_TB0.2_COM3_S34-Pad13)") (class "Default")
      (node (ref "U1") (pin "13") (pinfunction "P6.6_TB0.2_COM3_S34_13") (pintype "bidirectional"))
    )
    (net (code "317") (name "unconnected-(U1-P6.7_TA0CLK_S26-Pad29)") (class "Default")
      (node (ref "U1") (pin "29") (pinfunction "P6.7_TA0CLK_S26_29") (pintype "bidirectional"))
    )
    (net (code "318") (name "unconnected-(U1-P7.0_TA0CLK_S13-Pad42)") (class "Default")
      (node (ref "U1") (pin "42") (pinfunction "P7.0_TA0CLK_S13_42") (pintype "bidirectional"))
    )
    (net (code "319") (name "unconnected-(U1-P7.1_TA0.0_S12-Pad43)") (class "Default")
      (node (ref "U1") (pin "43") (pinfunction "P7.1_TA0.0_S12_43") (pintype "bidirectional"))
    )
    (net (code "320") (name "unconnected-(U1-P7.2_TA0.1_S11-Pad44)") (class "Default")
      (node (ref "U1") (pin "44") (pinfunction "P7.2_TA0.1_S11_44") (pintype "bidirectional"))
    )
    (net (code "321") (name "unconnected-(U1-P7.3_TA0.2_S10-Pad45)") (class "Default")
      (node (ref "U1") (pin "45") (pinfunction "P7.3_TA0.2_S10_45") (pintype "bidirectional"))
    )
    (net (code "322") (name "unconnected-(U1-P7.5_TA0.2_S25-Pad30)") (class "Default")
      (node (ref "U1") (pin "30") (pinfunction "P7.5_TA0.2_S25_30") (pintype "bidirectional"))
    )
    (net (code "323") (name "unconnected-(U1-P7.6_TA0.1_S24-Pad31)") (class "Default")
      (node (ref "U1") (pin "31") (pinfunction "P7.6_TA0.1_S24_31") (pintype "bidirectional"))
    )
    (net (code "324") (name "unconnected-(U1-P7.7_TA1.2_TB0OUTH_S23-Pad32)") (class "Default")
      (node (ref "U1") (pin "32") (pinfunction "P7.7_TA1.2_TB0OUTH_S23_32") (pintype "bidirectional"))
    )
    (net (code "325") (name "unconnected-(U1-P9.0_ESICH0_ESITEST0_A8_C8-Pad52)") (class "Default")
      (node (ref "U1") (pin "52") (pinfunction "P9.0_ESICH0_ESITEST0_A8_C8_52") (pintype "bidirectional"))
    )
    (net (code "326") (name "unconnected-(U1-P9.1_ESICH1_ESITEST1_A9_C9-Pad53)") (class "Default")
      (node (ref "U1") (pin "53") (pinfunction "P9.1_ESICH1_ESITEST1_A9_C9_53") (pintype "bidirectional"))
    )
    (net (code "327") (name "unconnected-(U1-P9.2_ESICH2_ESITEST2_A10_C10-Pad54)") (class "Default")
      (node (ref "U1") (pin "54") (pinfunction "P9.2_ESICH2_ESITEST2_A10_C10_54") (pintype "bidirectional"))
    )
    (net (code "328") (name "unconnected-(U1-P9.3_ESICH3_ESITEST3_A11_C11-Pad55)") (class "Default")
      (node (ref "U1") (pin "55") (pinfunction "P9.3_ESICH3_ESITEST3_A11_C11_55") (pintype "bidirectional"))
    )
    (net (code "329") (name "unconnected-(U1-P9.4_ESICI0_A12_C12-Pad56)") (class "Default")
      (node (ref "U1") (pin "56") (pinfunction "P9.4_ESICI0_A12_C12_56") (pintype "bidirectional"))
    )
    (net (code "330") (name "unconnected-(U1-P9.5_ESICI1_A13_C13-Pad57)") (class "Default")
      (node (ref "U1") (pin "57") (pinfunction "P9.5_ESICI1_A13_C13_57") (pintype "bidirectional"))
    )
    (net (code "331") (name "unconnected-(U1-P9.6_ESICI2_A14_C14-Pad58)") (class "Default")
      (node (ref "U1") (pin "58") (pinfunction "P9.6_ESICI2_A14_C14_58") (pintype "bidirectional"))
    )
    (net (code "332") (name "unconnected-(U1-P9.7_ESICI3_A15_C15-Pad59)") (class "Default")
      (node (ref "U1") (pin "59") (pinfunction "P9.7_ESICI3_A15_C15_59") (pintype "bidirectional"))
    )
    (net (code "333") (name "unconnected-(U1-PJ.0_TDO_TB0OUTH_SMCLK_SRSCG1-Pad25)") (class "Default")
      (node (ref "U1") (pin "25") (pinfunction "PJ.0_TDO_TB0OUTH_SMCLK_SRSCG1_25") (pintype "bidirectional"))
    )
    (net (code "334") (name "unconnected-(U1-PJ.1_TDI_TCLK_MCLK_SRSCG0-Pad26)") (class "Default")
      (node (ref "U1") (pin "26") (pinfunction "PJ.1_TDI_TCLK_MCLK_SRSCG0_26") (pintype "bidirectional"))
    )
    (net (code "335") (name "unconnected-(U1-PJ.2_TMS_ACLK_SROSCOFF-Pad27)") (class "Default")
      (node (ref "U1") (pin "27") (pinfunction "PJ.2_TMS_ACLK_SROSCOFF_27") (pintype "bidirectional"))
    )
    (net (code "336") (name "unconnected-(U1-PJ.3_TCK_COUT_SRCPUOFF-Pad28)") (class "Default")
      (node (ref "U1") (pin "28") (pinfunction "PJ.3_TCK_COUT_SRCPUOFF_28") (pintype "bidirectional"))
    )
    (net (code "337") (name "unconnected-(U1-PJ.6_HFXIN-Pad67)") (class "Default")
      (node (ref "U1") (pin "67") (pinfunction "PJ.6_HFXIN_67") (pintype "bidirectional"))
    )
    (net (code "338") (name "unconnected-(U1-PJ.7_HFXOUT-Pad66)") (class "Default")
      (node (ref "U1") (pin "66") (pinfunction "PJ.7_HFXOUT_66") (pintype "bidirectional"))
    )
    (net (code "339") (name "unconnected-(U1-R33_LCDCAP-Pad6)") (class "Default")
      (node (ref "U1") (pin "6") (pinfunction "R33_LCDCAP_6") (pintype "passive"))
    )
    (net (code "340") (name "unconnected-(U12-VIN3-Pad6)") (class "Default")
      (node (ref "U12") (pin "6") (pinfunction "VIN3_6") (pintype "bidirectional"))
    )
    (net (code "341") (name "unconnected-(U13-VIN3-Pad6)") (class "Default")
      (node (ref "U13") (pin "6") (pinfunction "VIN3_6") (pintype "bidirectional"))
    )
    (net (code "342") (name "unconnected-(U17-VIN3-Pad6)") (class "Default")
      (node (ref "U17") (pin "6") (pinfunction "VIN3_6") (pintype "bidirectional"))
    )
    (net (code "343") (name "unconnected-(U18-VIN3-Pad6)") (class "Default")
      (node (ref "U18") (pin "6") (pinfunction "VIN3_6") (pintype "bidirectional"))
    )
    (net (code "344") (name "unconnected-(U19-STAT-Pad1)") (class "Default")
      (node (ref "U19") (pin "1") (pinfunction "STAT_1") (pintype "bidirectional"))
    )
  )
)
